# REV1.net
KiCad netlist of a schematic drawn in EAGLE
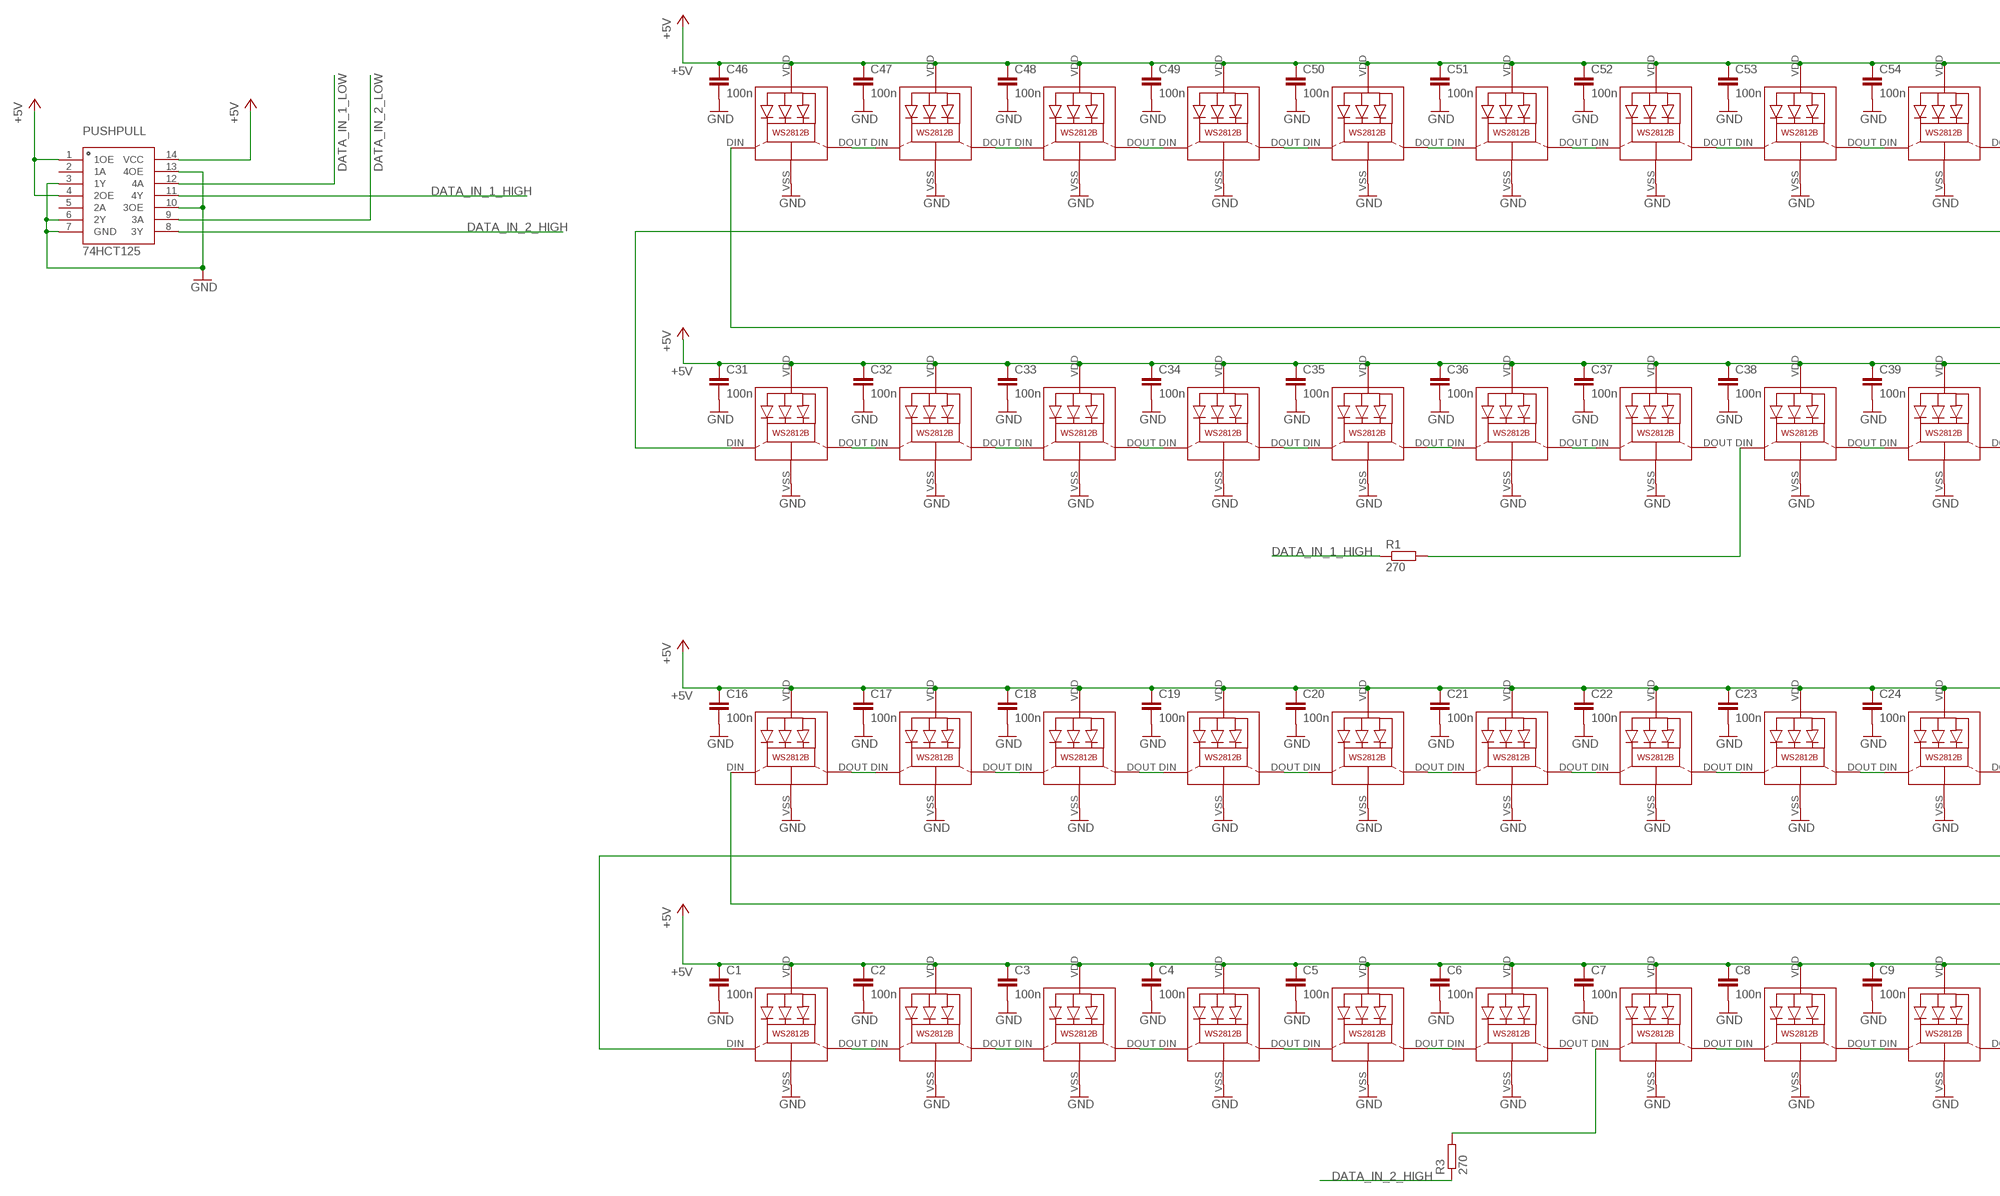
[diagram p0: schematic, sheet 1, part 1 of 2]
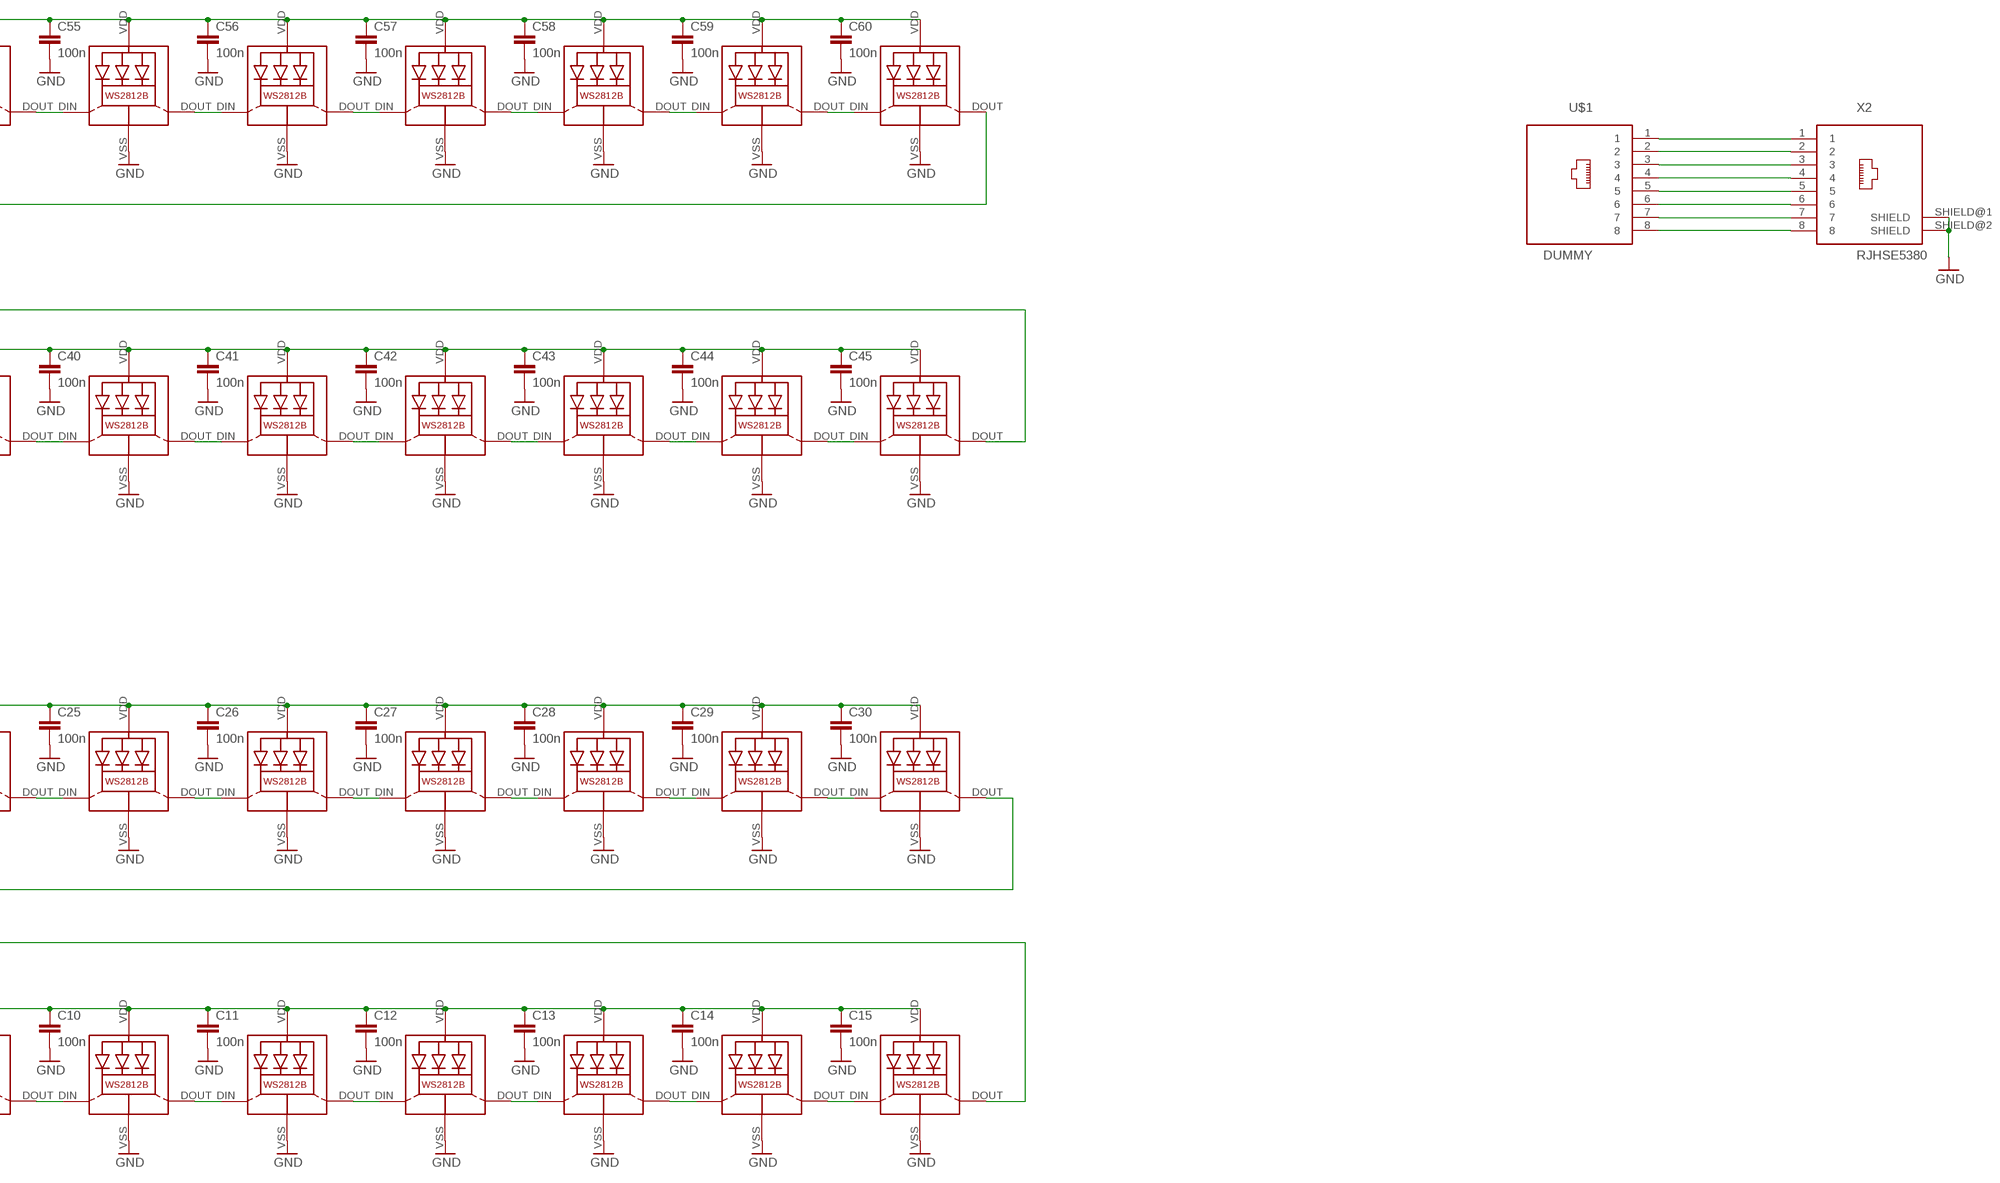
[diagram p1: schematic, sheet 1, part 2 of 2]
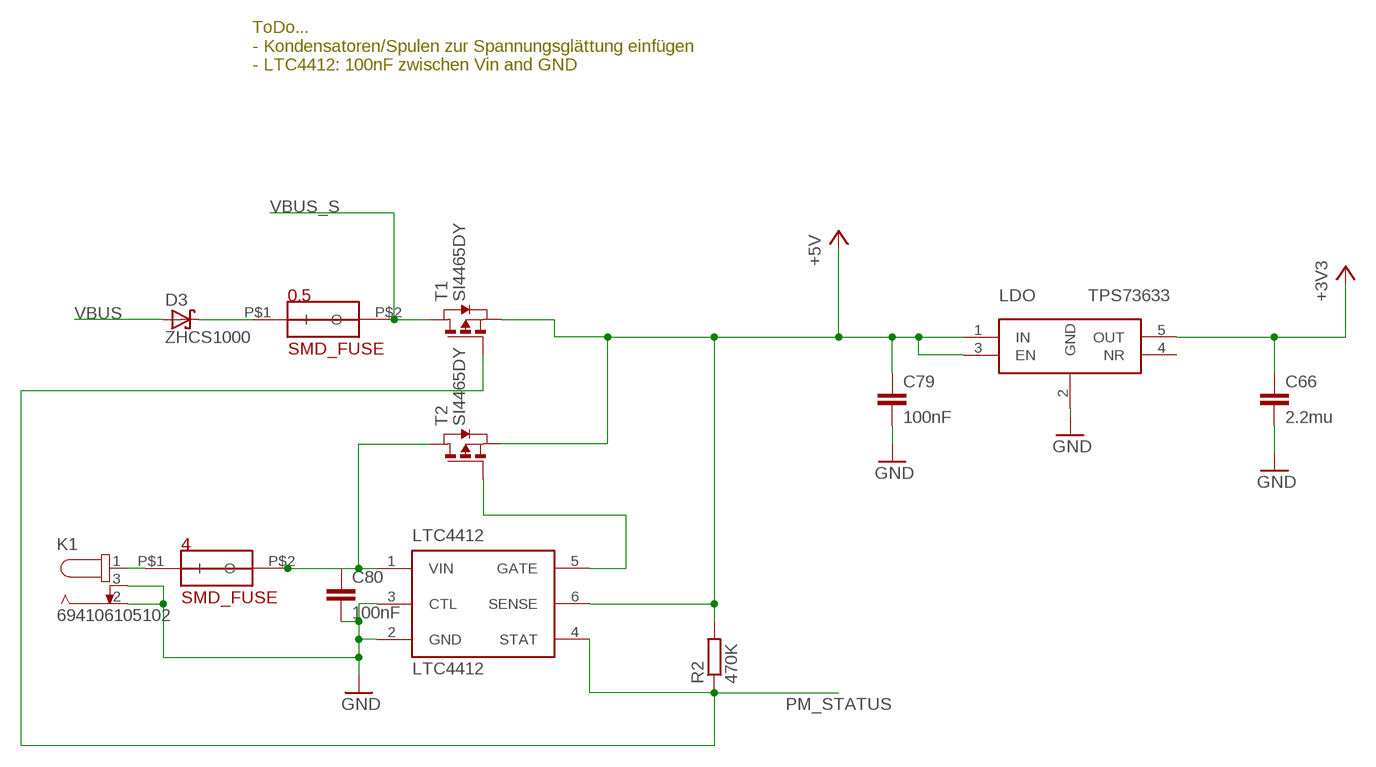
[diagram p2: schematic, sheet 2]
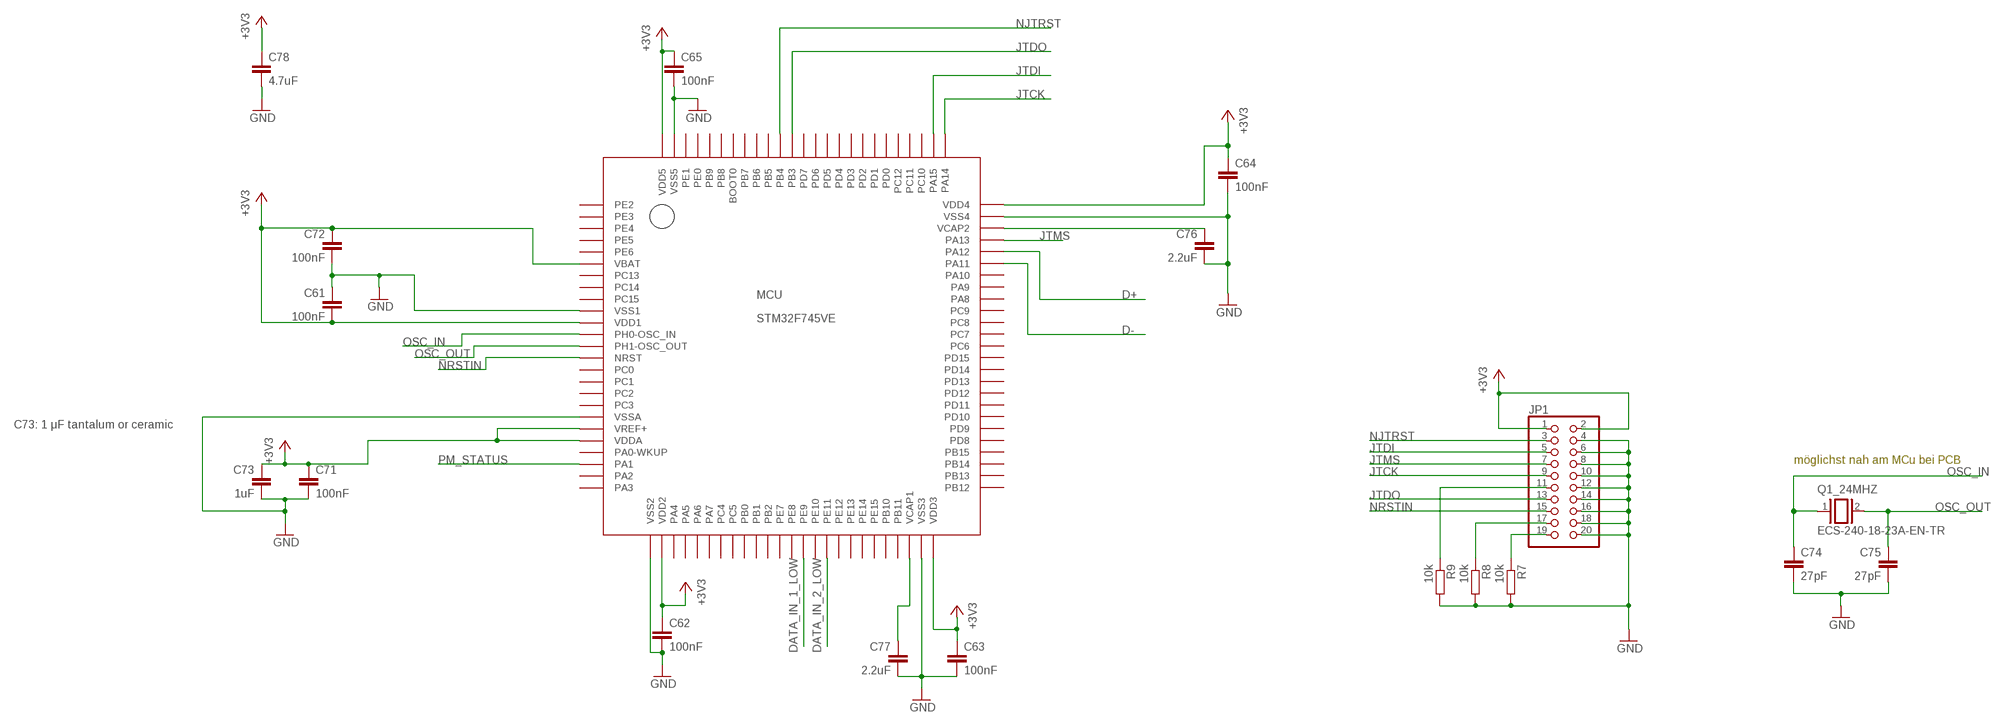
[diagram p3: schematic, sheet 3]
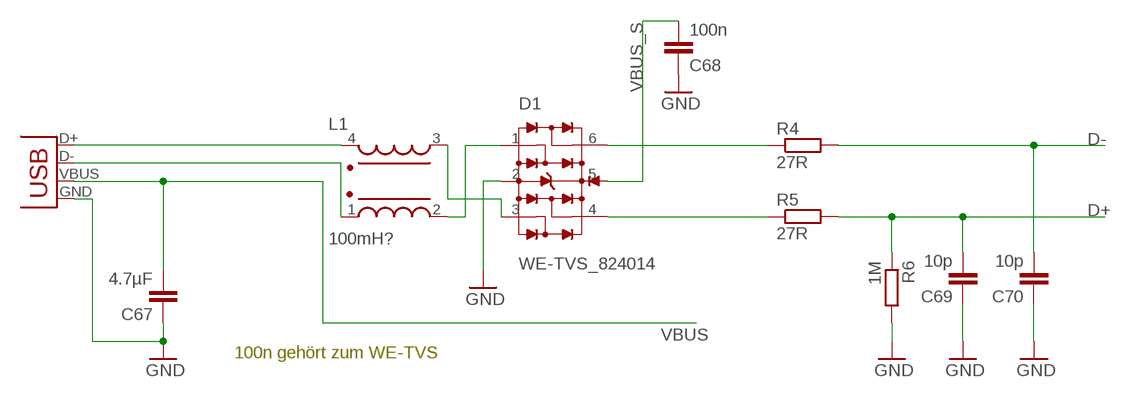
[diagram p4: schematic, sheet 4]

(export (version "E")
  (design (tool "Eeschema 10.0.6"))
  (components
    (comp (ref "C61")
      (value "100nF")
      (footprint "eagle-import:C0603")
      (libsource (lib "eagle-import") (part "C-EUC0603"))
    )
    (comp (ref "C62")
      (value "100nF")
      (footprint "eagle-import:C0603")
      (libsource (lib "eagle-import") (part "C-EUC0603"))
    )
    (comp (ref "C63")
      (value "100nF")
      (footprint "eagle-import:C0603")
      (libsource (lib "eagle-import") (part "C-EUC0603"))
    )
    (comp (ref "C64")
      (value "100nF")
      (footprint "eagle-import:C0603")
      (libsource (lib "eagle-import") (part "C-EUC0603"))
    )
    (comp (ref "C65")
      (value "100nF")
      (footprint "eagle-import:C0603")
      (libsource (lib "eagle-import") (part "C-EUC0603"))
    )
    (comp (ref "C71")
      (value "100nF")
      (footprint "eagle-import:C0603")
      (libsource (lib "eagle-import") (part "C-EUC0603"))
    )
    (comp (ref "C72")
      (value "100nF")
      (footprint "eagle-import:C0603")
      (libsource (lib "eagle-import") (part "C-EUC0603"))
    )
    (comp (ref "C73")
      (value "1uF")
      (footprint "eagle-import:C0603")
      (libsource (lib "eagle-import") (part "C-EUC0603"))
    )
    (comp (ref "C74")
      (value "27pF")
      (footprint "eagle-import:C0603")
      (libsource (lib "eagle-import") (part "C-EUC0603"))
    )
    (comp (ref "C75")
      (value "27pF")
      (footprint "eagle-import:C0603")
      (libsource (lib "eagle-import") (part "C-EUC0603"))
    )
    (comp (ref "C76")
      (value "2.2uF")
      (footprint "eagle-import:C0603")
      (libsource (lib "eagle-import") (part "C-EUC0603"))
    )
    (comp (ref "C77")
      (value "2.2uF")
      (footprint "eagle-import:C0603")
      (libsource (lib "eagle-import") (part "C-EUC0603"))
    )
    (comp (ref "C78")
      (value "4.7uF")
      (footprint "eagle-import:C0603")
      (libsource (lib "eagle-import") (part "C-EUC0603"))
    )
    (comp (ref "JP1")
      (value "PINHD-2X10_2.54-SMD")
      (footprint "eagle-import:2X10SMD")
      (libsource (lib "eagle-import") (part "PINHD-2X10_2.54-SMD"))
    )
    (comp (ref "MCU")
      (value "STM32F745VE")
      (footprint "eagle-import:LQFP100")
      (libsource (lib "eagle-import") (part "STM32F745VE"))
    )
    (comp (ref "Q1_24MHZ")
      (value "ECS-240-18-23A-EN-TR")
      (footprint "eagle-import:ESC64A")
      (libsource (lib "eagle-import") (part "ECX64A"))
    )
    (comp (ref "R7")
      (value "10k")
      (footprint "eagle-import:R0603")
      (libsource (lib "eagle-import") (part "R-EU_R0603"))
    )
    (comp (ref "R8")
      (value "10k")
      (footprint "eagle-import:R0603")
      (libsource (lib "eagle-import") (part "R-EU_R0603"))
    )
    (comp (ref "R9")
      (value "10k")
      (footprint "eagle-import:R0603")
      (libsource (lib "eagle-import") (part "R-EU_R0603"))
    )
    (comp (ref "C1")
      (value "100n")
      (footprint "eagle-import:C0603")
      (libsource (lib "eagle-import") (part "C-EUC0603"))
    )
    (comp (ref "C2")
      (value "100n")
      (footprint "eagle-import:C0603")
      (libsource (lib "eagle-import") (part "C-EUC0603"))
    )
    (comp (ref "C3")
      (value "100n")
      (footprint "eagle-import:C0603")
      (libsource (lib "eagle-import") (part "C-EUC0603"))
    )
    (comp (ref "C4")
      (value "100n")
      (footprint "eagle-import:C0603")
      (libsource (lib "eagle-import") (part "C-EUC0603"))
    )
    (comp (ref "C5")
      (value "100n")
      (footprint "eagle-import:C0603")
      (libsource (lib "eagle-import") (part "C-EUC0603"))
    )
    (comp (ref "C6")
      (value "100n")
      (footprint "eagle-import:C0603")
      (libsource (lib "eagle-import") (part "C-EUC0603"))
    )
    (comp (ref "C7")
      (value "100n")
      (footprint "eagle-import:C0603")
      (libsource (lib "eagle-import") (part "C-EUC0603"))
    )
    (comp (ref "C8")
      (value "100n")
      (footprint "eagle-import:C0603")
      (libsource (lib "eagle-import") (part "C-EUC0603"))
    )
    (comp (ref "C9")
      (value "100n")
      (footprint "eagle-import:C0603")
      (libsource (lib "eagle-import") (part "C-EUC0603"))
    )
    (comp (ref "C10")
      (value "100n")
      (footprint "eagle-import:C0603")
      (libsource (lib "eagle-import") (part "C-EUC0603"))
    )
    (comp (ref "C11")
      (value "100n")
      (footprint "eagle-import:C0603")
      (libsource (lib "eagle-import") (part "C-EUC0603"))
    )
    (comp (ref "C12")
      (value "100n")
      (footprint "eagle-import:C0603")
      (libsource (lib "eagle-import") (part "C-EUC0603"))
    )
    (comp (ref "C13")
      (value "100n")
      (footprint "eagle-import:C0603")
      (libsource (lib "eagle-import") (part "C-EUC0603"))
    )
    (comp (ref "C14")
      (value "100n")
      (footprint "eagle-import:C0603")
      (libsource (lib "eagle-import") (part "C-EUC0603"))
    )
    (comp (ref "C15")
      (value "100n")
      (footprint "eagle-import:C0603")
      (libsource (lib "eagle-import") (part "C-EUC0603"))
    )
    (comp (ref "C16")
      (value "100n")
      (footprint "eagle-import:C0603")
      (libsource (lib "eagle-import") (part "C-EUC0603"))
    )
    (comp (ref "C17")
      (value "100n")
      (footprint "eagle-import:C0603")
      (libsource (lib "eagle-import") (part "C-EUC0603"))
    )
    (comp (ref "C18")
      (value "100n")
      (footprint "eagle-import:C0603")
      (libsource (lib "eagle-import") (part "C-EUC0603"))
    )
    (comp (ref "C19")
      (value "100n")
      (footprint "eagle-import:C0603")
      (libsource (lib "eagle-import") (part "C-EUC0603"))
    )
    (comp (ref "C20")
      (value "100n")
      (footprint "eagle-import:C0603")
      (libsource (lib "eagle-import") (part "C-EUC0603"))
    )
    (comp (ref "C21")
      (value "100n")
      (footprint "eagle-import:C0603")
      (libsource (lib "eagle-import") (part "C-EUC0603"))
    )
    (comp (ref "C22")
      (value "100n")
      (footprint "eagle-import:C0603")
      (libsource (lib "eagle-import") (part "C-EUC0603"))
    )
    (comp (ref "C23")
      (value "100n")
      (footprint "eagle-import:C0603")
      (libsource (lib "eagle-import") (part "C-EUC0603"))
    )
    (comp (ref "C24")
      (value "100n")
      (footprint "eagle-import:C0603")
      (libsource (lib "eagle-import") (part "C-EUC0603"))
    )
    (comp (ref "C25")
      (value "100n")
      (footprint "eagle-import:C0603")
      (libsource (lib "eagle-import") (part "C-EUC0603"))
    )
    (comp (ref "C26")
      (value "100n")
      (footprint "eagle-import:C0603")
      (libsource (lib "eagle-import") (part "C-EUC0603"))
    )
    (comp (ref "C27")
      (value "100n")
      (footprint "eagle-import:C0603")
      (libsource (lib "eagle-import") (part "C-EUC0603"))
    )
    (comp (ref "C28")
      (value "100n")
      (footprint "eagle-import:C0603")
      (libsource (lib "eagle-import") (part "C-EUC0603"))
    )
    (comp (ref "C29")
      (value "100n")
      (footprint "eagle-import:C0603")
      (libsource (lib "eagle-import") (part "C-EUC0603"))
    )
    (comp (ref "C30")
      (value "100n")
      (footprint "eagle-import:C0603")
      (libsource (lib "eagle-import") (part "C-EUC0603"))
    )
    (comp (ref "C31")
      (value "100n")
      (footprint "eagle-import:C0603")
      (libsource (lib "eagle-import") (part "C-EUC0603"))
    )
    (comp (ref "C32")
      (value "100n")
      (footprint "eagle-import:C0603")
      (libsource (lib "eagle-import") (part "C-EUC0603"))
    )
    (comp (ref "C33")
      (value "100n")
      (footprint "eagle-import:C0603")
      (libsource (lib "eagle-import") (part "C-EUC0603"))
    )
    (comp (ref "C34")
      (value "100n")
      (footprint "eagle-import:C0603")
      (libsource (lib "eagle-import") (part "C-EUC0603"))
    )
    (comp (ref "C35")
      (value "100n")
      (footprint "eagle-import:C0603")
      (libsource (lib "eagle-import") (part "C-EUC0603"))
    )
    (comp (ref "C36")
      (value "100n")
      (footprint "eagle-import:C0603")
      (libsource (lib "eagle-import") (part "C-EUC0603"))
    )
    (comp (ref "C37")
      (value "100n")
      (footprint "eagle-import:C0603")
      (libsource (lib "eagle-import") (part "C-EUC0603"))
    )
    (comp (ref "C38")
      (value "100n")
      (footprint "eagle-import:C0603")
      (libsource (lib "eagle-import") (part "C-EUC0603"))
    )
    (comp (ref "C39")
      (value "100n")
      (footprint "eagle-import:C0603")
      (libsource (lib "eagle-import") (part "C-EUC0603"))
    )
    (comp (ref "C40")
      (value "100n")
      (footprint "eagle-import:C0603")
      (libsource (lib "eagle-import") (part "C-EUC0603"))
    )
    (comp (ref "C41")
      (value "100n")
      (footprint "eagle-import:C0603")
      (libsource (lib "eagle-import") (part "C-EUC0603"))
    )
    (comp (ref "C42")
      (value "100n")
      (footprint "eagle-import:C0603")
      (libsource (lib "eagle-import") (part "C-EUC0603"))
    )
    (comp (ref "C43")
      (value "100n")
      (footprint "eagle-import:C0603")
      (libsource (lib "eagle-import") (part "C-EUC0603"))
    )
    (comp (ref "C44")
      (value "100n")
      (footprint "eagle-import:C0603")
      (libsource (lib "eagle-import") (part "C-EUC0603"))
    )
    (comp (ref "C45")
      (value "100n")
      (footprint "eagle-import:C0603")
      (libsource (lib "eagle-import") (part "C-EUC0603"))
    )
    (comp (ref "C46")
      (value "100n")
      (footprint "eagle-import:C0603")
      (libsource (lib "eagle-import") (part "C-EUC0603"))
    )
    (comp (ref "C47")
      (value "100n")
      (footprint "eagle-import:C0603")
      (libsource (lib "eagle-import") (part "C-EUC0603"))
    )
    (comp (ref "C48")
      (value "100n")
      (footprint "eagle-import:C0603")
      (libsource (lib "eagle-import") (part "C-EUC0603"))
    )
    (comp (ref "C49")
      (value "100n")
      (footprint "eagle-import:C0603")
      (libsource (lib "eagle-import") (part "C-EUC0603"))
    )
    (comp (ref "C50")
      (value "100n")
      (footprint "eagle-import:C0603")
      (libsource (lib "eagle-import") (part "C-EUC0603"))
    )
    (comp (ref "C51")
      (value "100n")
      (footprint "eagle-import:C0603")
      (libsource (lib "eagle-import") (part "C-EUC0603"))
    )
    (comp (ref "C52")
      (value "100n")
      (footprint "eagle-import:C0603")
      (libsource (lib "eagle-import") (part "C-EUC0603"))
    )
    (comp (ref "C53")
      (value "100n")
      (footprint "eagle-import:C0603")
      (libsource (lib "eagle-import") (part "C-EUC0603"))
    )
    (comp (ref "C54")
      (value "100n")
      (footprint "eagle-import:C0603")
      (libsource (lib "eagle-import") (part "C-EUC0603"))
    )
    (comp (ref "C55")
      (value "100n")
      (footprint "eagle-import:C0603")
      (libsource (lib "eagle-import") (part "C-EUC0603"))
    )
    (comp (ref "C56")
      (value "100n")
      (footprint "eagle-import:C0603")
      (libsource (lib "eagle-import") (part "C-EUC0603"))
    )
    (comp (ref "C57")
      (value "100n")
      (footprint "eagle-import:C0603")
      (libsource (lib "eagle-import") (part "C-EUC0603"))
    )
    (comp (ref "C58")
      (value "100n")
      (footprint "eagle-import:C0603")
      (libsource (lib "eagle-import") (part "C-EUC0603"))
    )
    (comp (ref "C59")
      (value "100n")
      (footprint "eagle-import:C0603")
      (libsource (lib "eagle-import") (part "C-EUC0603"))
    )
    (comp (ref "C60")
      (value "100n")
      (footprint "eagle-import:C0603")
      (libsource (lib "eagle-import") (part "C-EUC0603"))
    )
    (comp (ref "LED1")
      (value "WS2812B")
      (footprint "eagle-import:WS2812B")
      (libsource (lib "eagle-import") (part "WS2812B"))
    )
    (comp (ref "LED2")
      (value "WS2812B")
      (footprint "eagle-import:WS2812B")
      (libsource (lib "eagle-import") (part "WS2812B"))
    )
    (comp (ref "LED3")
      (value "WS2812B")
      (footprint "eagle-import:WS2812B")
      (libsource (lib "eagle-import") (part "WS2812B"))
    )
    (comp (ref "LED4")
      (value "WS2812B")
      (footprint "eagle-import:WS2812B")
      (libsource (lib "eagle-import") (part "WS2812B"))
    )
    (comp (ref "LED5")
      (value "WS2812B")
      (footprint "eagle-import:WS2812B")
      (libsource (lib "eagle-import") (part "WS2812B"))
    )
    (comp (ref "LED6")
      (value "WS2812B")
      (footprint "eagle-import:WS2812B")
      (libsource (lib "eagle-import") (part "WS2812B"))
    )
    (comp (ref "LED7")
      (value "WS2812B")
      (footprint "eagle-import:WS2812B")
      (libsource (lib "eagle-import") (part "WS2812B"))
    )
    (comp (ref "LED8")
      (value "WS2812B")
      (footprint "eagle-import:WS2812B")
      (libsource (lib "eagle-import") (part "WS2812B"))
    )
    (comp (ref "LED9")
      (value "WS2812B")
      (footprint "eagle-import:WS2812B")
      (libsource (lib "eagle-import") (part "WS2812B"))
    )
    (comp (ref "LED10")
      (value "WS2812B")
      (footprint "eagle-import:WS2812B")
      (libsource (lib "eagle-import") (part "WS2812B"))
    )
    (comp (ref "LED11")
      (value "WS2812B")
      (footprint "eagle-import:WS2812B")
      (libsource (lib "eagle-import") (part "WS2812B"))
    )
    (comp (ref "LED12")
      (value "WS2812B")
      (footprint "eagle-import:WS2812B")
      (libsource (lib "eagle-import") (part "WS2812B"))
    )
    (comp (ref "LED13")
      (value "WS2812B")
      (footprint "eagle-import:WS2812B")
      (libsource (lib "eagle-import") (part "WS2812B"))
    )
    (comp (ref "LED14")
      (value "WS2812B")
      (footprint "eagle-import:WS2812B")
      (libsource (lib "eagle-import") (part "WS2812B"))
    )
    (comp (ref "LED15")
      (value "WS2812B")
      (footprint "eagle-import:WS2812B")
      (libsource (lib "eagle-import") (part "WS2812B"))
    )
    (comp (ref "LED16")
      (value "WS2812B")
      (footprint "eagle-import:WS2812B")
      (libsource (lib "eagle-import") (part "WS2812B"))
    )
    (comp (ref "LED17")
      (value "WS2812B")
      (footprint "eagle-import:WS2812B")
      (libsource (lib "eagle-import") (part "WS2812B"))
    )
    (comp (ref "LED18")
      (value "WS2812B")
      (footprint "eagle-import:WS2812B")
      (libsource (lib "eagle-import") (part "WS2812B"))
    )
    (comp (ref "LED19")
      (value "WS2812B")
      (footprint "eagle-import:WS2812B")
      (libsource (lib "eagle-import") (part "WS2812B"))
    )
    (comp (ref "LED20")
      (value "WS2812B")
      (footprint "eagle-import:WS2812B")
      (libsource (lib "eagle-import") (part "WS2812B"))
    )
    (comp (ref "LED21")
      (value "WS2812B")
      (footprint "eagle-import:WS2812B")
      (libsource (lib "eagle-import") (part "WS2812B"))
    )
    (comp (ref "LED22")
      (value "WS2812B")
      (footprint "eagle-import:WS2812B")
      (libsource (lib "eagle-import") (part "WS2812B"))
    )
    (comp (ref "LED23")
      (value "WS2812B")
      (footprint "eagle-import:WS2812B")
      (libsource (lib "eagle-import") (part "WS2812B"))
    )
    (comp (ref "LED24")
      (value "WS2812B")
      (footprint "eagle-import:WS2812B")
      (libsource (lib "eagle-import") (part "WS2812B"))
    )
    (comp (ref "LED25")
      (value "WS2812B")
      (footprint "eagle-import:WS2812B")
      (libsource (lib "eagle-import") (part "WS2812B"))
    )
    (comp (ref "LED26")
      (value "WS2812B")
      (footprint "eagle-import:WS2812B")
      (libsource (lib "eagle-import") (part "WS2812B"))
    )
    (comp (ref "LED27")
      (value "WS2812B")
      (footprint "eagle-import:WS2812B")
      (libsource (lib "eagle-import") (part "WS2812B"))
    )
    (comp (ref "LED28")
      (value "WS2812B")
      (footprint "eagle-import:WS2812B")
      (libsource (lib "eagle-import") (part "WS2812B"))
    )
    (comp (ref "LED29")
      (value "WS2812B")
      (footprint "eagle-import:WS2812B")
      (libsource (lib "eagle-import") (part "WS2812B"))
    )
    (comp (ref "LED30")
      (value "WS2812B")
      (footprint "eagle-import:WS2812B")
      (libsource (lib "eagle-import") (part "WS2812B"))
    )
    (comp (ref "LED31")
      (value "WS2812B")
      (footprint "eagle-import:WS2812B")
      (libsource (lib "eagle-import") (part "WS2812B"))
    )
    (comp (ref "LED32")
      (value "WS2812B")
      (footprint "eagle-import:WS2812B")
      (libsource (lib "eagle-import") (part "WS2812B"))
    )
    (comp (ref "LED33")
      (value "WS2812B")
      (footprint "eagle-import:WS2812B")
      (libsource (lib "eagle-import") (part "WS2812B"))
    )
    (comp (ref "LED34")
      (value "WS2812B")
      (footprint "eagle-import:WS2812B")
      (libsource (lib "eagle-import") (part "WS2812B"))
    )
    (comp (ref "LED35")
      (value "WS2812B")
      (footprint "eagle-import:WS2812B")
      (libsource (lib "eagle-import") (part "WS2812B"))
    )
    (comp (ref "LED36")
      (value "WS2812B")
      (footprint "eagle-import:WS2812B")
      (libsource (lib "eagle-import") (part "WS2812B"))
    )
    (comp (ref "LED37")
      (value "WS2812B")
      (footprint "eagle-import:WS2812B")
      (libsource (lib "eagle-import") (part "WS2812B"))
    )
    (comp (ref "LED38")
      (value "WS2812B")
      (footprint "eagle-import:WS2812B")
      (libsource (lib "eagle-import") (part "WS2812B"))
    )
    (comp (ref "LED39")
      (value "WS2812B")
      (footprint "eagle-import:WS2812B")
      (libsource (lib "eagle-import") (part "WS2812B"))
    )
    (comp (ref "LED40")
      (value "WS2812B")
      (footprint "eagle-import:WS2812B")
      (libsource (lib "eagle-import") (part "WS2812B"))
    )
    (comp (ref "LED41")
      (value "WS2812B")
      (footprint "eagle-import:WS2812B")
      (libsource (lib "eagle-import") (part "WS2812B"))
    )
    (comp (ref "LED42")
      (value "WS2812B")
      (footprint "eagle-import:WS2812B")
      (libsource (lib "eagle-import") (part "WS2812B"))
    )
    (comp (ref "LED43")
      (value "WS2812B")
      (footprint "eagle-import:WS2812B")
      (libsource (lib "eagle-import") (part "WS2812B"))
    )
    (comp (ref "LED44")
      (value "WS2812B")
      (footprint "eagle-import:WS2812B")
      (libsource (lib "eagle-import") (part "WS2812B"))
    )
    (comp (ref "LED45")
      (value "WS2812B")
      (footprint "eagle-import:WS2812B")
      (libsource (lib "eagle-import") (part "WS2812B"))
    )
    (comp (ref "LED46")
      (value "WS2812B")
      (footprint "eagle-import:WS2812B")
      (libsource (lib "eagle-import") (part "WS2812B"))
    )
    (comp (ref "LED47")
      (value "WS2812B")
      (footprint "eagle-import:WS2812B")
      (libsource (lib "eagle-import") (part "WS2812B"))
    )
    (comp (ref "LED48")
      (value "WS2812B")
      (footprint "eagle-import:WS2812B")
      (libsource (lib "eagle-import") (part "WS2812B"))
    )
    (comp (ref "LED49")
      (value "WS2812B")
      (footprint "eagle-import:WS2812B")
      (libsource (lib "eagle-import") (part "WS2812B"))
    )
    (comp (ref "LED50")
      (value "WS2812B")
      (footprint "eagle-import:WS2812B")
      (libsource (lib "eagle-import") (part "WS2812B"))
    )
    (comp (ref "LED51")
      (value "WS2812B")
      (footprint "eagle-import:WS2812B")
      (libsource (lib "eagle-import") (part "WS2812B"))
    )
    (comp (ref "LED52")
      (value "WS2812B")
      (footprint "eagle-import:WS2812B")
      (libsource (lib "eagle-import") (part "WS2812B"))
    )
    (comp (ref "LED53")
      (value "WS2812B")
      (footprint "eagle-import:WS2812B")
      (libsource (lib "eagle-import") (part "WS2812B"))
    )
    (comp (ref "LED54")
      (value "WS2812B")
      (footprint "eagle-import:WS2812B")
      (libsource (lib "eagle-import") (part "WS2812B"))
    )
    (comp (ref "LED55")
      (value "WS2812B")
      (footprint "eagle-import:WS2812B")
      (libsource (lib "eagle-import") (part "WS2812B"))
    )
    (comp (ref "LED56")
      (value "WS2812B")
      (footprint "eagle-import:WS2812B")
      (libsource (lib "eagle-import") (part "WS2812B"))
    )
    (comp (ref "LED57")
      (value "WS2812B")
      (footprint "eagle-import:WS2812B")
      (libsource (lib "eagle-import") (part "WS2812B"))
    )
    (comp (ref "LED58")
      (value "WS2812B")
      (footprint "eagle-import:WS2812B")
      (libsource (lib "eagle-import") (part "WS2812B"))
    )
    (comp (ref "LED59")
      (value "WS2812B")
      (footprint "eagle-import:WS2812B")
      (libsource (lib "eagle-import") (part "WS2812B"))
    )
    (comp (ref "LED60")
      (value "WS2812B")
      (footprint "eagle-import:WS2812B")
      (libsource (lib "eagle-import") (part "WS2812B"))
    )
    (comp (ref "PUSHPULL")
      (value "74HCT125")
      (footprint "eagle-import:SO-14DW")
      (libsource (lib "eagle-import") (part "74HCT125"))
    )
    (comp (ref "R1")
      (value "270")
      (footprint "eagle-import:R0603")
      (libsource (lib "eagle-import") (part "R-EU_R0603"))
    )
    (comp (ref "R3")
      (value "270")
      (footprint "eagle-import:R0603")
      (libsource (lib "eagle-import") (part "R-EU_R0603"))
    )
    (comp (ref "U$1")
      (value "DUMMY")
      (footprint "eagle-import:DUMMY")
      (libsource (lib "eagle-import") (part "DUMMY"))
    )
    (comp (ref "X2")
      (value "RJHSE5380")
      (footprint "eagle-import:RJHSE5380")
      (libsource (lib "eagle-import") (part "RJHSE5380"))
    )
    (comp (ref "C67")
      (value "4.7µF")
      (footprint "eagle-import:C0603")
      (libsource (lib "eagle-import") (part "C-EUC0603"))
    )
    (comp (ref "C68")
      (value "100n")
      (footprint "eagle-import:C0603")
      (libsource (lib "eagle-import") (part "C-EUC0603"))
    )
    (comp (ref "C69")
      (value "10p")
      (footprint "eagle-import:C0603")
      (libsource (lib "eagle-import") (part "C-EUC0603"))
    )
    (comp (ref "C70")
      (value "10p")
      (footprint "eagle-import:C0603")
      (libsource (lib "eagle-import") (part "C-EUC0603"))
    )
    (comp (ref "D1")
      (value "WE-TVS_824014")
      (footprint "eagle-import:WE-TVS_SOT23-6L")
      (libsource (lib "eagle-import") (part "WE-TVS_824014"))
    )
    (comp (ref "L1")
      (value "100mH?")
      (footprint "eagle-import:WE-CNSW_0805")
      (libsource (lib "eagle-import") (part "WE-CNSW_0805"))
    )
    (comp (ref "R4")
      (value "27R")
      (footprint "eagle-import:R0603")
      (libsource (lib "eagle-import") (part "R-EU_R0603"))
    )
    (comp (ref "R5")
      (value "27R")
      (footprint "eagle-import:R0603")
      (libsource (lib "eagle-import") (part "R-EU_R0603"))
    )
    (comp (ref "R6")
      (value "1M")
      (footprint "eagle-import:R0603")
      (libsource (lib "eagle-import") (part "R-EU_R0603"))
    )
    (comp (ref "X1")
      (value "USBSMD")
      (footprint "eagle-import:USB-MINIB")
      (libsource (lib "eagle-import") (part "USBSMD"))
    )
    (comp (ref "0.5")
      (value "SMD_FUSE")
      (footprint "eagle-import:FUSE")
      (libsource (lib "eagle-import") (part "SMD_FUSE"))
    )
    (comp (ref "4")
      (value "SMD_FUSE")
      (footprint "eagle-import:FUSE")
      (libsource (lib "eagle-import") (part "SMD_FUSE"))
    )
    (comp (ref "C66")
      (value "2.2mu")
      (footprint "eagle-import:C0603")
      (libsource (lib "eagle-import") (part "C-EUC0603"))
    )
    (comp (ref "C79")
      (value "100nF")
      (footprint "eagle-import:C0603")
      (libsource (lib "eagle-import") (part "C-EUC0603"))
    )
    (comp (ref "C80")
      (value "100nF")
      (footprint "eagle-import:C0603")
      (libsource (lib "eagle-import") (part "C-EUC0603"))
    )
    (comp (ref "D3")
      (value "ZHCS1000")
      (footprint "eagle-import:SOT23")
      (libsource (lib "eagle-import") (part "ZHCS1000"))
    )
    (comp (ref "K1")
      (value "694106105102")
      (footprint "eagle-import:694106105102")
      (libsource (lib "eagle-import") (part "694106105102"))
    )
    (comp (ref "LDO")
      (value "TPS73633")
      (footprint "eagle-import:SOT23-DBV")
      (libsource (lib "eagle-import") (part "TPS73633"))
    )
    (comp (ref "LTC4412")
      (value "LTC4412")
      (footprint "eagle-import:SOT23-6L")
      (libsource (lib "eagle-import") (part "LTC4412"))
    )
    (comp (ref "R2")
      (value "470K")
      (footprint "eagle-import:R0603")
      (libsource (lib "eagle-import") (part "R-EU_R0603"))
    )
    (comp (ref "T1")
      (value "SI4465DY")
      (footprint "eagle-import:SO08")
      (libsource (lib "eagle-import") (part "PMOSSOT223SO8"))
    )
    (comp (ref "T2")
      (value "SI4465DY")
      (footprint "eagle-import:SO08")
      (libsource (lib "eagle-import") (part "PMOSSOT223SO8"))
    )
  )
  (nets
    (net (code "1") (name "+3V3") (class "Default")
      (node (ref "C61") (pin "2") (pinfunction "2_2") (pintype "passive"))
      (node (ref "C62") (pin "1") (pinfunction "1_1") (pintype "passive"))
      (node (ref "C63") (pin "1") (pinfunction "1_1") (pintype "passive"))
      (node (ref "C64") (pin "1") (pinfunction "1_1") (pintype "passive"))
      (node (ref "C65") (pin "1") (pinfunction "1_1") (pintype "passive"))
      (node (ref "C66") (pin "1") (pinfunction "1_1") (pintype "passive"))
      (node (ref "C71") (pin "1") (pinfunction "1_1") (pintype "passive"))
      (node (ref "C72") (pin "1") (pinfunction "1_1") (pintype "passive"))
      (node (ref "C73") (pin "1") (pinfunction "1_1") (pintype "passive"))
      (node (ref "C78") (pin "1") (pinfunction "1_1") (pintype "passive"))
      (node (ref "JP1") (pin "1") (pinfunction "1_1") (pintype "passive"))
      (node (ref "JP1") (pin "2") (pinfunction "2_2") (pintype "passive"))
      (node (ref "LDO") (pin "5") (pinfunction "OUT_5") (pintype "bidirectional"))
      (node (ref "MCU") (pin "100") (pinfunction "VDD5_100") (pintype "power_in"))
      (node (ref "MCU") (pin "11") (pinfunction "VDD1_11") (pintype "power_in"))
      (node (ref "MCU") (pin "20") (pinfunction "VREF+_20") (pintype "power_in"))
      (node (ref "MCU") (pin "21") (pinfunction "VDDA_21") (pintype "power_in"))
      (node (ref "MCU") (pin "27") (pinfunction "VDD2_27") (pintype "power_in"))
      (node (ref "MCU") (pin "50") (pinfunction "VDD3_50") (pintype "power_in"))
      (node (ref "MCU") (pin "6") (pinfunction "VBAT_6") (pintype "power_in"))
      (node (ref "MCU") (pin "75") (pinfunction "VDD4_75") (pintype "power_in"))
    )
    (net (code "2") (name "+5V") (class "Default")
      (node (ref "C1") (pin "1") (pinfunction "1_1") (pintype "passive"))
      (node (ref "C10") (pin "1") (pinfunction "1_1") (pintype "passive"))
      (node (ref "C11") (pin "1") (pinfunction "1_1") (pintype "passive"))
      (node (ref "C12") (pin "1") (pinfunction "1_1") (pintype "passive"))
      (node (ref "C13") (pin "1") (pinfunction "1_1") (pintype "passive"))
      (node (ref "C14") (pin "1") (pinfunction "1_1") (pintype "passive"))
      (node (ref "C15") (pin "1") (pinfunction "1_1") (pintype "passive"))
      (node (ref "C16") (pin "1") (pinfunction "1_1") (pintype "passive"))
      (node (ref "C17") (pin "1") (pinfunction "1_1") (pintype "passive"))
      (node (ref "C18") (pin "1") (pinfunction "1_1") (pintype "passive"))
      (node (ref "C19") (pin "1") (pinfunction "1_1") (pintype "passive"))
      (node (ref "C2") (pin "1") (pinfunction "1_1") (pintype "passive"))
      (node (ref "C20") (pin "1") (pinfunction "1_1") (pintype "passive"))
      (node (ref "C21") (pin "1") (pinfunction "1_1") (pintype "passive"))
      (node (ref "C22") (pin "1") (pinfunction "1_1") (pintype "passive"))
      (node (ref "C23") (pin "1") (pinfunction "1_1") (pintype "passive"))
      (node (ref "C24") (pin "1") (pinfunction "1_1") (pintype "passive"))
      (node (ref "C25") (pin "1") (pinfunction "1_1") (pintype "passive"))
      (node (ref "C26") (pin "1") (pinfunction "1_1") (pintype "passive"))
      (node (ref "C27") (pin "1") (pinfunction "1_1") (pintype "passive"))
      (node (ref "C28") (pin "1") (pinfunction "1_1") (pintype "passive"))
      (node (ref "C29") (pin "1") (pinfunction "1_1") (pintype "passive"))
      (node (ref "C3") (pin "1") (pinfunction "1_1") (pintype "passive"))
      (node (ref "C30") (pin "1") (pinfunction "1_1") (pintype "passive"))
      (node (ref "C31") (pin "1") (pinfunction "1_1") (pintype "passive"))
      (node (ref "C32") (pin "1") (pinfunction "1_1") (pintype "passive"))
      (node (ref "C33") (pin "1") (pinfunction "1_1") (pintype "passive"))
      (node (ref "C34") (pin "1") (pinfunction "1_1") (pintype "passive"))
      (node (ref "C35") (pin "1") (pinfunction "1_1") (pintype "passive"))
      (node (ref "C36") (pin "1") (pinfunction "1_1") (pintype "passive"))
      (node (ref "C37") (pin "1") (pinfunction "1_1") (pintype "passive"))
      (node (ref "C38") (pin "1") (pinfunction "1_1") (pintype "passive"))
      (node (ref "C39") (pin "1") (pinfunction "1_1") (pintype "passive"))
      (node (ref "C4") (pin "1") (pinfunction "1_1") (pintype "passive"))
      (node (ref "C40") (pin "1") (pinfunction "1_1") (pintype "passive"))
      (node (ref "C41") (pin "1") (pinfunction "1_1") (pintype "passive"))
      (node (ref "C42") (pin "1") (pinfunction "1_1") (pintype "passive"))
      (node (ref "C43") (pin "1") (pinfunction "1_1") (pintype "passive"))
      (node (ref "C44") (pin "1") (pinfunction "1_1") (pintype "passive"))
      (node (ref "C45") (pin "1") (pinfunction "1_1") (pintype "passive"))
      (node (ref "C46") (pin "1") (pinfunction "1_1") (pintype "passive"))
      (node (ref "C47") (pin "1") (pinfunction "1_1") (pintype "passive"))
      (node (ref "C48") (pin "1") (pinfunction "1_1") (pintype "passive"))
      (node (ref "C49") (pin "1") (pinfunction "1_1") (pintype "passive"))
      (node (ref "C5") (pin "1") (pinfunction "1_1") (pintype "passive"))
      (node (ref "C50") (pin "1") (pinfunction "1_1") (pintype "passive"))
      (node (ref "C51") (pin "1") (pinfunction "1_1") (pintype "passive"))
      (node (ref "C52") (pin "1") (pinfunction "1_1") (pintype "passive"))
      (node (ref "C53") (pin "1") (pinfunction "1_1") (pintype "passive"))
      (node (ref "C54") (pin "1") (pinfunction "1_1") (pintype "passive"))
      (node (ref "C55") (pin "1") (pinfunction "1_1") (pintype "passive"))
      (node (ref "C56") (pin "1") (pinfunction "1_1") (pintype "passive"))
      (node (ref "C57") (pin "1") (pinfunction "1_1") (pintype "passive"))
      (node (ref "C58") (pin "1") (pinfunction "1_1") (pintype "passive"))
      (node (ref "C59") (pin "1") (pinfunction "1_1") (pintype "passive"))
      (node (ref "C6") (pin "1") (pinfunction "1_1") (pintype "passive"))
      (node (ref "C60") (pin "1") (pinfunction "1_1") (pintype "passive"))
      (node (ref "C7") (pin "1") (pinfunction "1_1") (pintype "passive"))
      (node (ref "C79") (pin "1") (pinfunction "1_1") (pintype "passive"))
      (node (ref "C8") (pin "1") (pinfunction "1_1") (pintype "passive"))
      (node (ref "C9") (pin "1") (pinfunction "1_1") (pintype "passive"))
      (node (ref "LDO") (pin "1") (pinfunction "IN_1") (pintype "bidirectional"))
      (node (ref "LDO") (pin "3") (pinfunction "EN_3") (pintype "bidirectional"))
      (node (ref "LED1") (pin "VDD") (pinfunction "VDD_VDD") (pintype "power_in"))
      (node (ref "LED10") (pin "VDD") (pinfunction "VDD_VDD") (pintype "power_in"))
      (node (ref "LED11") (pin "VDD") (pinfunction "VDD_VDD") (pintype "power_in"))
      (node (ref "LED12") (pin "VDD") (pinfunction "VDD_VDD") (pintype "power_in"))
      (node (ref "LED13") (pin "VDD") (pinfunction "VDD_VDD") (pintype "power_in"))
      (node (ref "LED14") (pin "VDD") (pinfunction "VDD_VDD") (pintype "power_in"))
      (node (ref "LED15") (pin "VDD") (pinfunction "VDD_VDD") (pintype "power_in"))
      (node (ref "LED16") (pin "VDD") (pinfunction "VDD_VDD") (pintype "power_in"))
      (node (ref "LED17") (pin "VDD") (pinfunction "VDD_VDD") (pintype "power_in"))
      (node (ref "LED18") (pin "VDD") (pinfunction "VDD_VDD") (pintype "power_in"))
      (node (ref "LED19") (pin "VDD") (pinfunction "VDD_VDD") (pintype "power_in"))
      (node (ref "LED2") (pin "VDD") (pinfunction "VDD_VDD") (pintype "power_in"))
      (node (ref "LED20") (pin "VDD") (pinfunction "VDD_VDD") (pintype "power_in"))
      (node (ref "LED21") (pin "VDD") (pinfunction "VDD_VDD") (pintype "power_in"))
      (node (ref "LED22") (pin "VDD") (pinfunction "VDD_VDD") (pintype "power_in"))
      (node (ref "LED23") (pin "VDD") (pinfunction "VDD_VDD") (pintype "power_in"))
      (node (ref "LED24") (pin "VDD") (pinfunction "VDD_VDD") (pintype "power_in"))
      (node (ref "LED25") (pin "VDD") (pinfunction "VDD_VDD") (pintype "power_in"))
      (node (ref "LED26") (pin "VDD") (pinfunction "VDD_VDD") (pintype "power_in"))
      (node (ref "LED27") (pin "VDD") (pinfunction "VDD_VDD") (pintype "power_in"))
      (node (ref "LED28") (pin "VDD") (pinfunction "VDD_VDD") (pintype "power_in"))
      (node (ref "LED29") (pin "VDD") (pinfunction "VDD_VDD") (pintype "power_in"))
      (node (ref "LED3") (pin "VDD") (pinfunction "VDD_VDD") (pintype "power_in"))
      (node (ref "LED30") (pin "VDD") (pinfunction "VDD_VDD") (pintype "power_in"))
      (node (ref "LED31") (pin "VDD") (pinfunction "VDD_VDD") (pintype "power_in"))
      (node (ref "LED32") (pin "VDD") (pinfunction "VDD_VDD") (pintype "power_in"))
      (node (ref "LED33") (pin "VDD") (pinfunction "VDD_VDD") (pintype "power_in"))
      (node (ref "LED34") (pin "VDD") (pinfunction "VDD_VDD") (pintype "power_in"))
      (node (ref "LED35") (pin "VDD") (pinfunction "VDD_VDD") (pintype "power_in"))
      (node (ref "LED36") (pin "VDD") (pinfunction "VDD_VDD") (pintype "power_in"))
      (node (ref "LED37") (pin "VDD") (pinfunction "VDD_VDD") (pintype "power_in"))
      (node (ref "LED38") (pin "VDD") (pinfunction "VDD_VDD") (pintype "power_in"))
      (node (ref "LED39") (pin "VDD") (pinfunction "VDD_VDD") (pintype "power_in"))
      (node (ref "LED4") (pin "VDD") (pinfunction "VDD_VDD") (pintype "power_in"))
      (node (ref "LED40") (pin "VDD") (pinfunction "VDD_VDD") (pintype "power_in"))
      (node (ref "LED41") (pin "VDD") (pinfunction "VDD_VDD") (pintype "power_in"))
      (node (ref "LED42") (pin "VDD") (pinfunction "VDD_VDD") (pintype "power_in"))
      (node (ref "LED43") (pin "VDD") (pinfunction "VDD_VDD") (pintype "power_in"))
      (node (ref "LED44") (pin "VDD") (pinfunction "VDD_VDD") (pintype "power_in"))
      (node (ref "LED45") (pin "VDD") (pinfunction "VDD_VDD") (pintype "power_in"))
      (node (ref "LED46") (pin "VDD") (pinfunction "VDD_VDD") (pintype "power_in"))
      (node (ref "LED47") (pin "VDD") (pinfunction "VDD_VDD") (pintype "power_in"))
      (node (ref "LED48") (pin "VDD") (pinfunction "VDD_VDD") (pintype "power_in"))
      (node (ref "LED49") (pin "VDD") (pinfunction "VDD_VDD") (pintype "power_in"))
      (node (ref "LED5") (pin "VDD") (pinfunction "VDD_VDD") (pintype "power_in"))
      (node (ref "LED50") (pin "VDD") (pinfunction "VDD_VDD") (pintype "power_in"))
      (node (ref "LED51") (pin "VDD") (pinfunction "VDD_VDD") (pintype "power_in"))
      (node (ref "LED52") (pin "VDD") (pinfunction "VDD_VDD") (pintype "power_in"))
      (node (ref "LED53") (pin "VDD") (pinfunction "VDD_VDD") (pintype "power_in"))
      (node (ref "LED54") (pin "VDD") (pinfunction "VDD_VDD") (pintype "power_in"))
      (node (ref "LED55") (pin "VDD") (pinfunction "VDD_VDD") (pintype "power_in"))
      (node (ref "LED56") (pin "VDD") (pinfunction "VDD_VDD") (pintype "power_in"))
      (node (ref "LED57") (pin "VDD") (pinfunction "VDD_VDD") (pintype "power_in"))
      (node (ref "LED58") (pin "VDD") (pinfunction "VDD_VDD") (pintype "power_in"))
      (node (ref "LED59") (pin "VDD") (pinfunction "VDD_VDD") (pintype "power_in"))
      (node (ref "LED6") (pin "VDD") (pinfunction "VDD_VDD") (pintype "power_in"))
      (node (ref "LED60") (pin "VDD") (pinfunction "VDD_VDD") (pintype "power_in"))
      (node (ref "LED7") (pin "VDD") (pinfunction "VDD_VDD") (pintype "power_in"))
      (node (ref "LED8") (pin "VDD") (pinfunction "VDD_VDD") (pintype "power_in"))
      (node (ref "LED9") (pin "VDD") (pinfunction "VDD_VDD") (pintype "power_in"))
      (node (ref "LTC4412") (pin "6") (pinfunction "SENSE_6") (pintype "bidirectional"))
      (node (ref "PUSHPULL") (pin "1") (pinfunction "1OE_1") (pintype "bidirectional"))
      (node (ref "PUSHPULL") (pin "14") (pinfunction "VCC_14") (pintype "bidirectional"))
      (node (ref "PUSHPULL") (pin "4") (pinfunction "2OE_4") (pintype "bidirectional"))
      (node (ref "R2") (pin "2") (pinfunction "2_2") (pintype "passive"))
      (node (ref "T1") (pin "1") (pinfunction "S_1") (pintype "passive"))
      (node (ref "T1") (pin "2") (pinfunction "S_2") (pintype "passive"))
      (node (ref "T1") (pin "3") (pinfunction "S_3") (pintype "passive"))
      (node (ref "T2") (pin "1") (pinfunction "S_1") (pintype "passive"))
      (node (ref "T2") (pin "2") (pinfunction "S_2") (pintype "passive"))
      (node (ref "T2") (pin "3") (pinfunction "S_3") (pintype "passive"))
    )
    (net (code "3") (name "D+") (class "Default")
      (node (ref "C69") (pin "2") (pinfunction "2_2") (pintype "passive"))
      (node (ref "MCU") (pin "71") (pinfunction "PA12_71") (pintype "bidirectional"))
      (node (ref "R5") (pin "2") (pinfunction "2_2") (pintype "passive"))
      (node (ref "R6") (pin "1") (pinfunction "1_1") (pintype "passive"))
    )
    (net (code "4") (name "D-") (class "Default")
      (node (ref "C70") (pin "2") (pinfunction "2_2") (pintype "passive"))
      (node (ref "MCU") (pin "70") (pinfunction "PA11_70") (pintype "bidirectional"))
      (node (ref "R4") (pin "2") (pinfunction "2_2") (pintype "passive"))
    )
    (net (code "5") (name "DATA_IN_1_HIGH") (class "Default")
      (node (ref "PUSHPULL") (pin "11") (pinfunction "4Y_11") (pintype "bidirectional"))
      (node (ref "R1") (pin "1") (pinfunction "1_1") (pintype "passive"))
    )
    (net (code "6") (name "DATA_IN_1_LOW") (class "Default")
      (node (ref "MCU") (pin "39") (pinfunction "PE9_39") (pintype "bidirectional"))
      (node (ref "PUSHPULL") (pin "12") (pinfunction "4A_12") (pintype "bidirectional"))
    )
    (net (code "7") (name "DATA_IN_2_HIGH") (class "Default")
      (node (ref "PUSHPULL") (pin "8") (pinfunction "3Y_8") (pintype "bidirectional"))
      (node (ref "R3") (pin "1") (pinfunction "1_1") (pintype "passive"))
    )
    (net (code "8") (name "DATA_IN_2_LOW") (class "Default")
      (node (ref "MCU") (pin "41") (pinfunction "PE11_41") (pintype "bidirectional"))
      (node (ref "PUSHPULL") (pin "9") (pinfunction "3A_9") (pintype "bidirectional"))
    )
    (net (code "9") (name "GND") (class "Default")
      (node (ref "C1") (pin "2") (pinfunction "2_2") (pintype "passive"))
      (node (ref "C10") (pin "2") (pinfunction "2_2") (pintype "passive"))
      (node (ref "C11") (pin "2") (pinfunction "2_2") (pintype "passive"))
      (node (ref "C12") (pin "2") (pinfunction "2_2") (pintype "passive"))
      (node (ref "C13") (pin "2") (pinfunction "2_2") (pintype "passive"))
      (node (ref "C14") (pin "2") (pinfunction "2_2") (pintype "passive"))
      (node (ref "C15") (pin "2") (pinfunction "2_2") (pintype "passive"))
      (node (ref "C16") (pin "2") (pinfunction "2_2") (pintype "passive"))
      (node (ref "C17") (pin "2") (pinfunction "2_2") (pintype "passive"))
      (node (ref "C18") (pin "2") (pinfunction "2_2") (pintype "passive"))
      (node (ref "C19") (pin "2") (pinfunction "2_2") (pintype "passive"))
      (node (ref "C2") (pin "2") (pinfunction "2_2") (pintype "passive"))
      (node (ref "C20") (pin "2") (pinfunction "2_2") (pintype "passive"))
      (node (ref "C21") (pin "2") (pinfunction "2_2") (pintype "passive"))
      (node (ref "C22") (pin "2") (pinfunction "2_2") (pintype "passive"))
      (node (ref "C23") (pin "2") (pinfunction "2_2") (pintype "passive"))
      (node (ref "C24") (pin "2") (pinfunction "2_2") (pintype "passive"))
      (node (ref "C25") (pin "2") (pinfunction "2_2") (pintype "passive"))
      (node (ref "C26") (pin "2") (pinfunction "2_2") (pintype "passive"))
      (node (ref "C27") (pin "2") (pinfunction "2_2") (pintype "passive"))
      (node (ref "C28") (pin "2") (pinfunction "2_2") (pintype "passive"))
      (node (ref "C29") (pin "2") (pinfunction "2_2") (pintype "passive"))
      (node (ref "C3") (pin "2") (pinfunction "2_2") (pintype "passive"))
      (node (ref "C30") (pin "2") (pinfunction "2_2") (pintype "passive"))
      (node (ref "C31") (pin "2") (pinfunction "2_2") (pintype "passive"))
      (node (ref "C32") (pin "2") (pinfunction "2_2") (pintype "passive"))
      (node (ref "C33") (pin "2") (pinfunction "2_2") (pintype "passive"))
      (node (ref "C34") (pin "2") (pinfunction "2_2") (pintype "passive"))
      (node (ref "C35") (pin "2") (pinfunction "2_2") (pintype "passive"))
      (node (ref "C36") (pin "2") (pinfunction "2_2") (pintype "passive"))
      (node (ref "C37") (pin "2") (pinfunction "2_2") (pintype "passive"))
      (node (ref "C38") (pin "2") (pinfunction "2_2") (pintype "passive"))
      (node (ref "C39") (pin "2") (pinfunction "2_2") (pintype "passive"))
      (node (ref "C4") (pin "2") (pinfunction "2_2") (pintype "passive"))
      (node (ref "C40") (pin "2") (pinfunction "2_2") (pintype "passive"))
      (node (ref "C41") (pin "2") (pinfunction "2_2") (pintype "passive"))
      (node (ref "C42") (pin "2") (pinfunction "2_2") (pintype "passive"))
      (node (ref "C43") (pin "2") (pinfunction "2_2") (pintype "passive"))
      (node (ref "C44") (pin "2") (pinfunction "2_2") (pintype "passive"))
      (node (ref "C45") (pin "2") (pinfunction "2_2") (pintype "passive"))
      (node (ref "C46") (pin "2") (pinfunction "2_2") (pintype "passive"))
      (node (ref "C47") (pin "2") (pinfunction "2_2") (pintype "passive"))
      (node (ref "C48") (pin "2") (pinfunction "2_2") (pintype "passive"))
      (node (ref "C49") (pin "2") (pinfunction "2_2") (pintype "passive"))
      (node (ref "C5") (pin "2") (pinfunction "2_2") (pintype "passive"))
      (node (ref "C50") (pin "2") (pinfunction "2_2") (pintype "passive"))
      (node (ref "C51") (pin "2") (pinfunction "2_2") (pintype "passive"))
      (node (ref "C52") (pin "2") (pinfunction "2_2") (pintype "passive"))
      (node (ref "C53") (pin "2") (pinfunction "2_2") (pintype "passive"))
      (node (ref "C54") (pin "2") (pinfunction "2_2") (pintype "passive"))
      (node (ref "C55") (pin "2") (pinfunction "2_2") (pintype "passive"))
      (node (ref "C56") (pin "2") (pinfunction "2_2") (pintype "passive"))
      (node (ref "C57") (pin "2") (pinfunction "2_2") (pintype "passive"))
      (node (ref "C58") (pin "2") (pinfunction "2_2") (pintype "passive"))
      (node (ref "C59") (pin "2") (pinfunction "2_2") (pintype "passive"))
      (node (ref "C6") (pin "2") (pinfunction "2_2") (pintype "passive"))
      (node (ref "C60") (pin "2") (pinfunction "2_2") (pintype "passive"))
      (node (ref "C61") (pin "1") (pinfunction "1_1") (pintype "passive"))
      (node (ref "C62") (pin "2") (pinfunction "2_2") (pintype "passive"))
      (node (ref "C63") (pin "2") (pinfunction "2_2") (pintype "passive"))
      (node (ref "C64") (pin "2") (pinfunction "2_2") (pintype "passive"))
      (node (ref "C65") (pin "2") (pinfunction "2_2") (pintype "passive"))
      (node (ref "C66") (pin "2") (pinfunction "2_2") (pintype "passive"))
      (node (ref "C67") (pin "1") (pinfunction "1_1") (pintype "passive"))
      (node (ref "C68") (pin "1") (pinfunction "1_1") (pintype "passive"))
      (node (ref "C69") (pin "1") (pinfunction "1_1") (pintype "passive"))
      (node (ref "C7") (pin "2") (pinfunction "2_2") (pintype "passive"))
      (node (ref "C70") (pin "1") (pinfunction "1_1") (pintype "passive"))
      (node (ref "C71") (pin "2") (pinfunction "2_2") (pintype "passive"))
      (node (ref "C72") (pin "2") (pinfunction "2_2") (pintype "passive"))
      (node (ref "C73") (pin "2") (pinfunction "2_2") (pintype "passive"))
      (node (ref "C74") (pin "2") (pinfunction "2_2") (pintype "passive"))
      (node (ref "C75") (pin "2") (pinfunction "2_2") (pintype "passive"))
      (node (ref "C76") (pin "2") (pinfunction "2_2") (pintype "passive"))
      (node (ref "C77") (pin "2") (pinfunction "2_2") (pintype "passive"))
      (node (ref "C78") (pin "2") (pinfunction "2_2") (pintype "passive"))
      (node (ref "C79") (pin "2") (pinfunction "2_2") (pintype "passive"))
      (node (ref "C8") (pin "2") (pinfunction "2_2") (pintype "passive"))
      (node (ref "C80") (pin "2") (pinfunction "2_2") (pintype "passive"))
      (node (ref "C9") (pin "2") (pinfunction "2_2") (pintype "passive"))
      (node (ref "D1") (pin "2") (pinfunction "GND_2") (pintype "power_in"))
      (node (ref "JP1") (pin "10") (pinfunction "10_10") (pintype "passive"))
      (node (ref "JP1") (pin "12") (pinfunction "12_12") (pintype "passive"))
      (node (ref "JP1") (pin "14") (pinfunction "14_14") (pintype "passive"))
      (node (ref "JP1") (pin "16") (pinfunction "16_16") (pintype "passive"))
      (node (ref "JP1") (pin "18") (pinfunction "18_18") (pintype "passive"))
      (node (ref "JP1") (pin "20") (pinfunction "20_20") (pintype "passive"))
      (node (ref "JP1") (pin "4") (pinfunction "4_4") (pintype "passive"))
      (node (ref "JP1") (pin "6") (pinfunction "6_6") (pintype "passive"))
      (node (ref "JP1") (pin "8") (pinfunction "8_8") (pintype "passive"))
      (node (ref "K1") (pin "2") (pinfunction "2_2") (pintype "passive"))
      (node (ref "K1") (pin "3") (pinfunction "3_3") (pintype "passive"))
      (node (ref "LDO") (pin "2") (pinfunction "GND_2") (pintype "bidirectional"))
      (node (ref "LED1") (pin "VSS") (pinfunction "GND_VSS") (pintype "power_in"))
      (node (ref "LED10") (pin "VSS") (pinfunction "GND_VSS") (pintype "power_in"))
      (node (ref "LED11") (pin "VSS") (pinfunction "GND_VSS") (pintype "power_in"))
      (node (ref "LED12") (pin "VSS") (pinfunction "GND_VSS") (pintype "power_in"))
      (node (ref "LED13") (pin "VSS") (pinfunction "GND_VSS") (pintype "power_in"))
      (node (ref "LED14") (pin "VSS") (pinfunction "GND_VSS") (pintype "power_in"))
      (node (ref "LED15") (pin "VSS") (pinfunction "GND_VSS") (pintype "power_in"))
      (node (ref "LED16") (pin "VSS") (pinfunction "GND_VSS") (pintype "power_in"))
      (node (ref "LED17") (pin "VSS") (pinfunction "GND_VSS") (pintype "power_in"))
      (node (ref "LED18") (pin "VSS") (pinfunction "GND_VSS") (pintype "power_in"))
      (node (ref "LED19") (pin "VSS") (pinfunction "GND_VSS") (pintype "power_in"))
      (node (ref "LED2") (pin "VSS") (pinfunction "GND_VSS") (pintype "power_in"))
      (node (ref "LED20") (pin "VSS") (pinfunction "GND_VSS") (pintype "power_in"))
      (node (ref "LED21") (pin "VSS") (pinfunction "GND_VSS") (pintype "power_in"))
      (node (ref "LED22") (pin "VSS") (pinfunction "GND_VSS") (pintype "power_in"))
      (node (ref "LED23") (pin "VSS") (pinfunction "GND_VSS") (pintype "power_in"))
      (node (ref "LED24") (pin "VSS") (pinfunction "GND_VSS") (pintype "power_in"))
      (node (ref "LED25") (pin "VSS") (pinfunction "GND_VSS") (pintype "power_in"))
      (node (ref "LED26") (pin "VSS") (pinfunction "GND_VSS") (pintype "power_in"))
      (node (ref "LED27") (pin "VSS") (pinfunction "GND_VSS") (pintype "power_in"))
      (node (ref "LED28") (pin "VSS") (pinfunction "GND_VSS") (pintype "power_in"))
      (node (ref "LED29") (pin "VSS") (pinfunction "GND_VSS") (pintype "power_in"))
      (node (ref "LED3") (pin "VSS") (pinfunction "GND_VSS") (pintype "power_in"))
      (node (ref "LED30") (pin "VSS") (pinfunction "GND_VSS") (pintype "power_in"))
      (node (ref "LED31") (pin "VSS") (pinfunction "GND_VSS") (pintype "power_in"))
      (node (ref "LED32") (pin "VSS") (pinfunction "GND_VSS") (pintype "power_in"))
      (node (ref "LED33") (pin "VSS") (pinfunction "GND_VSS") (pintype "power_in"))
      (node (ref "LED34") (pin "VSS") (pinfunction "GND_VSS") (pintype "power_in"))
      (node (ref "LED35") (pin "VSS") (pinfunction "GND_VSS") (pintype "power_in"))
      (node (ref "LED36") (pin "VSS") (pinfunction "GND_VSS") (pintype "power_in"))
      (node (ref "LED37") (pin "VSS") (pinfunction "GND_VSS") (pintype "power_in"))
      (node (ref "LED38") (pin "VSS") (pinfunction "GND_VSS") (pintype "power_in"))
      (node (ref "LED39") (pin "VSS") (pinfunction "GND_VSS") (pintype "power_in"))
      (node (ref "LED4") (pin "VSS") (pinfunction "GND_VSS") (pintype "power_in"))
      (node (ref "LED40") (pin "VSS") (pinfunction "GND_VSS") (pintype "power_in"))
      (node (ref "LED41") (pin "VSS") (pinfunction "GND_VSS") (pintype "power_in"))
      (node (ref "LED42") (pin "VSS") (pinfunction "GND_VSS") (pintype "power_in"))
      (node (ref "LED43") (pin "VSS") (pinfunction "GND_VSS") (pintype "power_in"))
      (node (ref "LED44") (pin "VSS") (pinfunction "GND_VSS") (pintype "power_in"))
      (node (ref "LED45") (pin "VSS") (pinfunction "GND_VSS") (pintype "power_in"))
      (node (ref "LED46") (pin "VSS") (pinfunction "GND_VSS") (pintype "power_in"))
      (node (ref "LED47") (pin "VSS") (pinfunction "GND_VSS") (pintype "power_in"))
      (node (ref "LED48") (pin "VSS") (pinfunction "GND_VSS") (pintype "power_in"))
      (node (ref "LED49") (pin "VSS") (pinfunction "GND_VSS") (pintype "power_in"))
      (node (ref "LED5") (pin "VSS") (pinfunction "GND_VSS") (pintype "power_in"))
      (node (ref "LED50") (pin "VSS") (pinfunction "GND_VSS") (pintype "power_in"))
      (node (ref "LED51") (pin "VSS") (pinfunction "GND_VSS") (pintype "power_in"))
      (node (ref "LED52") (pin "VSS") (pinfunction "GND_VSS") (pintype "power_in"))
      (node (ref "LED53") (pin "VSS") (pinfunction "GND_VSS") (pintype "power_in"))
      (node (ref "LED54") (pin "VSS") (pinfunction "GND_VSS") (pintype "power_in"))
      (node (ref "LED55") (pin "VSS") (pinfunction "GND_VSS") (pintype "power_in"))
      (node (ref "LED56") (pin "VSS") (pinfunction "GND_VSS") (pintype "power_in"))
      (node (ref "LED57") (pin "VSS") (pinfunction "GND_VSS") (pintype "power_in"))
      (node (ref "LED58") (pin "VSS") (pinfunction "GND_VSS") (pintype "power_in"))
      (node (ref "LED59") (pin "VSS") (pinfunction "GND_VSS") (pintype "power_in"))
      (node (ref "LED6") (pin "VSS") (pinfunction "GND_VSS") (pintype "power_in"))
      (node (ref "LED60") (pin "VSS") (pinfunction "GND_VSS") (pintype "power_in"))
      (node (ref "LED7") (pin "VSS") (pinfunction "GND_VSS") (pintype "power_in"))
      (node (ref "LED8") (pin "VSS") (pinfunction "GND_VSS") (pintype "power_in"))
      (node (ref "LED9") (pin "VSS") (pinfunction "GND_VSS") (pintype "power_in"))
      (node (ref "LTC4412") (pin "2") (pinfunction "GND_2") (pintype "bidirectional"))
      (node (ref "LTC4412") (pin "3") (pinfunction "CTL_3") (pintype "bidirectional"))
      (node (ref "MCU") (pin "10") (pinfunction "VSS1_10") (pintype "power_in"))
      (node (ref "MCU") (pin "19") (pinfunction "VSSA_19") (pintype "power_in"))
      (node (ref "MCU") (pin "26") (pinfunction "VSS2_26") (pintype "power_in"))
      (node (ref "MCU") (pin "49") (pinfunction "VSS3_49") (pintype "power_in"))
      (node (ref "MCU") (pin "74") (pinfunction "VSS4_74") (pintype "power_in"))
      (node (ref "MCU") (pin "99") (pinfunction "VSS5_99") (pintype "power_in"))
      (node (ref "PUSHPULL") (pin "10") (pinfunction "3OE_10") (pintype "bidirectional"))
      (node (ref "PUSHPULL") (pin "13") (pinfunction "4OE_13") (pintype "bidirectional"))
      (node (ref "PUSHPULL") (pin "3") (pinfunction "1Y_3") (pintype "bidirectional"))
      (node (ref "PUSHPULL") (pin "6") (pinfunction "2Y_6") (pintype "bidirectional"))
      (node (ref "PUSHPULL") (pin "7") (pinfunction "GND_7") (pintype "bidirectional"))
      (node (ref "R6") (pin "2") (pinfunction "2_2") (pintype "passive"))
      (node (ref "R7") (pin "2") (pinfunction "2_2") (pintype "passive"))
      (node (ref "R8") (pin "2") (pinfunction "2_2") (pintype "passive"))
      (node (ref "R9") (pin "2") (pinfunction "2_2") (pintype "passive"))
      (node (ref "X1") (pin "GND") (pinfunction "GND_GND") (pintype "bidirectional"))
      (node (ref "X2") (pin "SHIELD@1") (pinfunction "SHIELD_SHIELD@1") (pintype "bidirectional"))
      (node (ref "X2") (pin "SHIELD@2") (pinfunction "SHIELD_SHIELD@2") (pintype "bidirectional"))
    )
    (net (code "10") (name "JTCK") (class "Default")
      (node (ref "JP1") (pin "9") (pinfunction "9_9") (pintype "passive"))
      (node (ref "MCU") (pin "76") (pinfunction "PA14_76") (pintype "bidirectional"))
    )
    (net (code "11") (name "JTDI") (class "Default")
      (node (ref "JP1") (pin "5") (pinfunction "5_5") (pintype "passive"))
      (node (ref "MCU") (pin "77") (pinfunction "PA15_77") (pintype "bidirectional"))
    )
    (net (code "12") (name "JTDO") (class "Default")
      (node (ref "JP1") (pin "13") (pinfunction "13_13") (pintype "passive"))
      (node (ref "MCU") (pin "89") (pinfunction "PB3_89") (pintype "bidirectional"))
    )
    (net (code "13") (name "JTMS") (class "Default")
      (node (ref "JP1") (pin "7") (pinfunction "7_7") (pintype "passive"))
      (node (ref "MCU") (pin "72") (pinfunction "PA13_72") (pintype "bidirectional"))
    )
    (net (code "14") (name "NJTRST") (class "Default")
      (node (ref "JP1") (pin "3") (pinfunction "3_3") (pintype "passive"))
      (node (ref "MCU") (pin "90") (pinfunction "PB4_90") (pintype "bidirectional"))
    )
    (net (code "15") (name "NRSTIN") (class "Default")
      (node (ref "JP1") (pin "15") (pinfunction "15_15") (pintype "passive"))
      (node (ref "MCU") (pin "14") (pinfunction "NRST_14") (pintype "bidirectional"))
    )
    (net (code "16") (name "Net-(0.5-I)") (class "Default")
      (node (ref "0.5") (pin "P$1") (pinfunction "I_P$1") (pintype "bidirectional"))
      (node (ref "D3") (pin "1") (pinfunction "C_1") (pintype "passive"))
    )
    (net (code "17") (name "Net-(4-I)") (class "Default")
      (node (ref "4") (pin "P$1") (pinfunction "I_P$1") (pintype "bidirectional"))
      (node (ref "K1") (pin "1") (pinfunction "1_1") (pintype "passive"))
    )
    (net (code "18") (name "Net-(4-O)") (class "Default")
      (node (ref "4") (pin "P$2") (pinfunction "O_P$2") (pintype "bidirectional"))
      (node (ref "C80") (pin "1") (pinfunction "1_1") (pintype "passive"))
      (node (ref "LTC4412") (pin "1") (pinfunction "VIN_1") (pintype "bidirectional"))
      (node (ref "T2") (pin "5") (pinfunction "D_5") (pintype "passive"))
      (node (ref "T2") (pin "6") (pinfunction "D_6") (pintype "passive"))
      (node (ref "T2") (pin "7") (pinfunction "D_7") (pintype "passive"))
      (node (ref "T2") (pin "8") (pinfunction "D_8") (pintype "passive"))
    )
    (net (code "19") (name "Net-(D1-2)") (class "Default")
      (node (ref "D1") (pin "3") (pinfunction "2_3") (pintype "passive"))
      (node (ref "L1") (pin "3") (pinfunction "2_3") (pintype "passive"))
    )
    (net (code "20") (name "Net-(D1-3)") (class "Default")
      (node (ref "D1") (pin "4") (pinfunction "3_4") (pintype "passive"))
      (node (ref "R5") (pin "1") (pinfunction "1_1") (pintype "passive"))
    )
    (net (code "21") (name "Net-(D1-4)") (class "Default")
      (node (ref "D1") (pin "6") (pinfunction "4_6") (pintype "passive"))
      (node (ref "R4") (pin "1") (pinfunction "1_1") (pintype "passive"))
    )
    (net (code "22") (name "Net-(JP1-Pad11)") (class "Default")
      (node (ref "JP1") (pin "11") (pinfunction "11_11") (pintype "passive"))
      (node (ref "R9") (pin "1") (pinfunction "1_1") (pintype "passive"))
    )
    (net (code "23") (name "Net-(JP1-Pad17)") (class "Default")
      (node (ref "JP1") (pin "17") (pinfunction "17_17") (pintype "passive"))
      (node (ref "R8") (pin "1") (pinfunction "1_1") (pintype "passive"))
    )
    (net (code "24") (name "Net-(JP1-Pad19)") (class "Default")
      (node (ref "JP1") (pin "19") (pinfunction "19_19") (pintype "passive"))
      (node (ref "R7") (pin "1") (pinfunction "1_1") (pintype "passive"))
    )
    (net (code "25") (name "Net-(L1-1)") (class "Default")
      (node (ref "L1") (pin "4") (pinfunction "1_4") (pintype "passive"))
      (node (ref "X1") (pin "D+") (pinfunction "D+_D+") (pintype "bidirectional"))
    )
    (net (code "26") (name "Net-(L1-3)") (class "Default")
      (node (ref "D1") (pin "1") (pinfunction "1_1") (pintype "passive"))
      (node (ref "L1") (pin "2") (pinfunction "3_2") (pintype "passive"))
    )
    (net (code "27") (name "Net-(L1-4)") (class "Default")
      (node (ref "L1") (pin "1") (pinfunction "4_1") (pintype "passive"))
      (node (ref "X1") (pin "D-") (pinfunction "D-_D-") (pintype "bidirectional"))
    )
    (net (code "28") (name "Net-(LED1-DI)") (class "Default")
      (node (ref "LED1") (pin "DIN") (pinfunction "DI_DIN") (pintype "input"))
      (node (ref "LED30") (pin "DOUT") (pinfunction "DO_DOUT") (pintype "output"))
    )
    (net (code "29") (name "Net-(LED1-DO)") (class "Default")
      (node (ref "LED1") (pin "DOUT") (pinfunction "DO_DOUT") (pintype "output"))
      (node (ref "LED2") (pin "DIN") (pinfunction "DI_DIN") (pintype "input"))
    )
    (net (code "30") (name "Net-(LED2-DO)") (class "Default")
      (node (ref "LED2") (pin "DOUT") (pinfunction "DO_DOUT") (pintype "output"))
      (node (ref "LED3") (pin "DIN") (pinfunction "DI_DIN") (pintype "input"))
    )
    (net (code "31") (name "Net-(LED3-DO)") (class "Default")
      (node (ref "LED3") (pin "DOUT") (pinfunction "DO_DOUT") (pintype "output"))
      (node (ref "LED4") (pin "DIN") (pinfunction "DI_DIN") (pintype "input"))
    )
    (net (code "32") (name "Net-(LED4-DO)") (class "Default")
      (node (ref "LED4") (pin "DOUT") (pinfunction "DO_DOUT") (pintype "output"))
      (node (ref "LED5") (pin "DIN") (pinfunction "DI_DIN") (pintype "input"))
    )
    (net (code "33") (name "Net-(LED5-DO)") (class "Default")
      (node (ref "LED5") (pin "DOUT") (pinfunction "DO_DOUT") (pintype "output"))
      (node (ref "LED6") (pin "DIN") (pinfunction "DI_DIN") (pintype "input"))
    )
    (net (code "34") (name "Net-(LED7-DI)") (class "Default")
      (node (ref "LED7") (pin "DIN") (pinfunction "DI_DIN") (pintype "input"))
      (node (ref "R3") (pin "2") (pinfunction "2_2") (pintype "passive"))
    )
    (net (code "35") (name "Net-(LED7-DO)") (class "Default")
      (node (ref "LED7") (pin "DOUT") (pinfunction "DO_DOUT") (pintype "output"))
      (node (ref "LED8") (pin "DIN") (pinfunction "DI_DIN") (pintype "input"))
    )
    (net (code "36") (name "Net-(LED8-DO)") (class "Default")
      (node (ref "LED8") (pin "DOUT") (pinfunction "DO_DOUT") (pintype "output"))
      (node (ref "LED9") (pin "DIN") (pinfunction "DI_DIN") (pintype "input"))
    )
    (net (code "37") (name "Net-(LED10-DI)") (class "Default")
      (node (ref "LED10") (pin "DIN") (pinfunction "DI_DIN") (pintype "input"))
      (node (ref "LED9") (pin "DOUT") (pinfunction "DO_DOUT") (pintype "output"))
    )
    (net (code "38") (name "Net-(LED10-DO)") (class "Default")
      (node (ref "LED10") (pin "DOUT") (pinfunction "DO_DOUT") (pintype "output"))
      (node (ref "LED11") (pin "DIN") (pinfunction "DI_DIN") (pintype "input"))
    )
    (net (code "39") (name "Net-(LED11-DO)") (class "Default")
      (node (ref "LED11") (pin "DOUT") (pinfunction "DO_DOUT") (pintype "output"))
      (node (ref "LED12") (pin "DIN") (pinfunction "DI_DIN") (pintype "input"))
    )
    (net (code "40") (name "Net-(LED12-DO)") (class "Default")
      (node (ref "LED12") (pin "DOUT") (pinfunction "DO_DOUT") (pintype "output"))
      (node (ref "LED13") (pin "DIN") (pinfunction "DI_DIN") (pintype "input"))
    )
    (net (code "41") (name "Net-(LED13-DO)") (class "Default")
      (node (ref "LED13") (pin "DOUT") (pinfunction "DO_DOUT") (pintype "output"))
      (node (ref "LED14") (pin "DIN") (pinfunction "DI_DIN") (pintype "input"))
    )
    (net (code "42") (name "Net-(LED14-DO)") (class "Default")
      (node (ref "LED14") (pin "DOUT") (pinfunction "DO_DOUT") (pintype "output"))
      (node (ref "LED15") (pin "DIN") (pinfunction "DI_DIN") (pintype "input"))
    )
    (net (code "43") (name "Net-(LED15-DO)") (class "Default")
      (node (ref "LED15") (pin "DOUT") (pinfunction "DO_DOUT") (pintype "output"))
      (node (ref "LED16") (pin "DIN") (pinfunction "DI_DIN") (pintype "input"))
    )
    (net (code "44") (name "Net-(LED16-DO)") (class "Default")
      (node (ref "LED16") (pin "DOUT") (pinfunction "DO_DOUT") (pintype "output"))
      (node (ref "LED17") (pin "DIN") (pinfunction "DI_DIN") (pintype "input"))
    )
    (net (code "45") (name "Net-(LED17-DO)") (class "Default")
      (node (ref "LED17") (pin "DOUT") (pinfunction "DO_DOUT") (pintype "output"))
      (node (ref "LED18") (pin "DIN") (pinfunction "DI_DIN") (pintype "input"))
    )
    (net (code "46") (name "Net-(LED18-DO)") (class "Default")
      (node (ref "LED18") (pin "DOUT") (pinfunction "DO_DOUT") (pintype "output"))
      (node (ref "LED19") (pin "DIN") (pinfunction "DI_DIN") (pintype "input"))
    )
    (net (code "47") (name "Net-(LED19-DO)") (class "Default")
      (node (ref "LED19") (pin "DOUT") (pinfunction "DO_DOUT") (pintype "output"))
      (node (ref "LED20") (pin "DIN") (pinfunction "DI_DIN") (pintype "input"))
    )
    (net (code "48") (name "Net-(LED20-DO)") (class "Default")
      (node (ref "LED20") (pin "DOUT") (pinfunction "DO_DOUT") (pintype "output"))
      (node (ref "LED21") (pin "DIN") (pinfunction "DI_DIN") (pintype "input"))
    )
    (net (code "49") (name "Net-(LED21-DO)") (class "Default")
      (node (ref "LED21") (pin "DOUT") (pinfunction "DO_DOUT") (pintype "output"))
      (node (ref "LED22") (pin "DIN") (pinfunction "DI_DIN") (pintype "input"))
    )
    (net (code "50") (name "Net-(LED22-DO)") (class "Default")
      (node (ref "LED22") (pin "DOUT") (pinfunction "DO_DOUT") (pintype "output"))
      (node (ref "LED23") (pin "DIN") (pinfunction "DI_DIN") (pintype "input"))
    )
    (net (code "51") (name "Net-(LED23-DO)") (class "Default")
      (node (ref "LED23") (pin "DOUT") (pinfunction "DO_DOUT") (pintype "output"))
      (node (ref "LED24") (pin "DIN") (pinfunction "DI_DIN") (pintype "input"))
    )
    (net (code "52") (name "Net-(LED24-DO)") (class "Default")
      (node (ref "LED24") (pin "DOUT") (pinfunction "DO_DOUT") (pintype "output"))
      (node (ref "LED25") (pin "DIN") (pinfunction "DI_DIN") (pintype "input"))
    )
    (net (code "53") (name "Net-(LED25-DO)") (class "Default")
      (node (ref "LED25") (pin "DOUT") (pinfunction "DO_DOUT") (pintype "output"))
      (node (ref "LED26") (pin "DIN") (pinfunction "DI_DIN") (pintype "input"))
    )
    (net (code "54") (name "Net-(LED26-DO)") (class "Default")
      (node (ref "LED26") (pin "DOUT") (pinfunction "DO_DOUT") (pintype "output"))
      (node (ref "LED27") (pin "DIN") (pinfunction "DI_DIN") (pintype "input"))
    )
    (net (code "55") (name "Net-(LED27-DO)") (class "Default")
      (node (ref "LED27") (pin "DOUT") (pinfunction "DO_DOUT") (pintype "output"))
      (node (ref "LED28") (pin "DIN") (pinfunction "DI_DIN") (pintype "input"))
    )
    (net (code "56") (name "Net-(LED28-DO)") (class "Default")
      (node (ref "LED28") (pin "DOUT") (pinfunction "DO_DOUT") (pintype "output"))
      (node (ref "LED29") (pin "DIN") (pinfunction "DI_DIN") (pintype "input"))
    )
    (net (code "57") (name "Net-(LED29-DO)") (class "Default")
      (node (ref "LED29") (pin "DOUT") (pinfunction "DO_DOUT") (pintype "output"))
      (node (ref "LED30") (pin "DIN") (pinfunction "DI_DIN") (pintype "input"))
    )
    (net (code "58") (name "Net-(LED31-DI)") (class "Default")
      (node (ref "LED31") (pin "DIN") (pinfunction "DI_DIN") (pintype "input"))
      (node (ref "LED60") (pin "DOUT") (pinfunction "DO_DOUT") (pintype "output"))
    )
    (net (code "59") (name "Net-(LED31-DO)") (class "Default")
      (node (ref "LED31") (pin "DOUT") (pinfunction "DO_DOUT") (pintype "output"))
      (node (ref "LED32") (pin "DIN") (pinfunction "DI_DIN") (pintype "input"))
    )
    (net (code "60") (name "Net-(LED32-DO)") (class "Default")
      (node (ref "LED32") (pin "DOUT") (pinfunction "DO_DOUT") (pintype "output"))
      (node (ref "LED33") (pin "DIN") (pinfunction "DI_DIN") (pintype "input"))
    )
    (net (code "61") (name "Net-(LED33-DO)") (class "Default")
      (node (ref "LED33") (pin "DOUT") (pinfunction "DO_DOUT") (pintype "output"))
      (node (ref "LED34") (pin "DIN") (pinfunction "DI_DIN") (pintype "input"))
    )
    (net (code "62") (name "Net-(LED34-DO)") (class "Default")
      (node (ref "LED34") (pin "DOUT") (pinfunction "DO_DOUT") (pintype "output"))
      (node (ref "LED35") (pin "DIN") (pinfunction "DI_DIN") (pintype "input"))
    )
    (net (code "63") (name "Net-(LED35-DO)") (class "Default")
      (node (ref "LED35") (pin "DOUT") (pinfunction "DO_DOUT") (pintype "output"))
      (node (ref "LED36") (pin "DIN") (pinfunction "DI_DIN") (pintype "input"))
    )
    (net (code "64") (name "Net-(LED36-DO)") (class "Default")
      (node (ref "LED36") (pin "DOUT") (pinfunction "DO_DOUT") (pintype "output"))
      (node (ref "LED37") (pin "DIN") (pinfunction "DI_DIN") (pintype "input"))
    )
    (net (code "65") (name "Net-(LED38-DI)") (class "Default")
      (node (ref "LED38") (pin "DIN") (pinfunction "DI_DIN") (pintype "input"))
      (node (ref "R1") (pin "2") (pinfunction "2_2") (pintype "passive"))
    )
    (net (code "66") (name "Net-(LED38-DO)") (class "Default")
      (node (ref "LED38") (pin "DOUT") (pinfunction "DO_DOUT") (pintype "output"))
      (node (ref "LED39") (pin "DIN") (pinfunction "DI_DIN") (pintype "input"))
    )
    (net (code "67") (name "Net-(LED39-DO)") (class "Default")
      (node (ref "LED39") (pin "DOUT") (pinfunction "DO_DOUT") (pintype "output"))
      (node (ref "LED40") (pin "DIN") (pinfunction "DI_DIN") (pintype "input"))
    )
    (net (code "68") (name "Net-(LED40-DO)") (class "Default")
      (node (ref "LED40") (pin "DOUT") (pinfunction "DO_DOUT") (pintype "output"))
      (node (ref "LED41") (pin "DIN") (pinfunction "DI_DIN") (pintype "input"))
    )
    (net (code "69") (name "Net-(LED41-DO)") (class "Default")
      (node (ref "LED41") (pin "DOUT") (pinfunction "DO_DOUT") (pintype "output"))
      (node (ref "LED42") (pin "DIN") (pinfunction "DI_DIN") (pintype "input"))
    )
    (net (code "70") (name "Net-(LED42-DO)") (class "Default")
      (node (ref "LED42") (pin "DOUT") (pinfunction "DO_DOUT") (pintype "output"))
      (node (ref "LED43") (pin "DIN") (pinfunction "DI_DIN") (pintype "input"))
    )
    (net (code "71") (name "Net-(LED43-DO)") (class "Default")
      (node (ref "LED43") (pin "DOUT") (pinfunction "DO_DOUT") (pintype "output"))
      (node (ref "LED44") (pin "DIN") (pinfunction "DI_DIN") (pintype "input"))
    )
    (net (code "72") (name "Net-(LED44-DO)") (class "Default")
      (node (ref "LED44") (pin "DOUT") (pinfunction "DO_DOUT") (pintype "output"))
      (node (ref "LED45") (pin "DIN") (pinfunction "DI_DIN") (pintype "input"))
    )
    (net (code "73") (name "Net-(LED45-DO)") (class "Default")
      (node (ref "LED45") (pin "DOUT") (pinfunction "DO_DOUT") (pintype "output"))
      (node (ref "LED46") (pin "DIN") (pinfunction "DI_DIN") (pintype "input"))
    )
    (net (code "74") (name "Net-(LED46-DO)") (class "Default")
      (node (ref "LED46") (pin "DOUT") (pinfunction "DO_DOUT") (pintype "output"))
      (node (ref "LED47") (pin "DIN") (pinfunction "DI_DIN") (pintype "input"))
    )
    (net (code "75") (name "Net-(LED47-DO)") (class "Default")
      (node (ref "LED47") (pin "DOUT") (pinfunction "DO_DOUT") (pintype "output"))
      (node (ref "LED48") (pin "DIN") (pinfunction "DI_DIN") (pintype "input"))
    )
    (net (code "76") (name "Net-(LED48-DO)") (class "Default")
      (node (ref "LED48") (pin "DOUT") (pinfunction "DO_DOUT") (pintype "output"))
      (node (ref "LED49") (pin "DIN") (pinfunction "DI_DIN") (pintype "input"))
    )
    (net (code "77") (name "Net-(LED49-DO)") (class "Default")
      (node (ref "LED49") (pin "DOUT") (pinfunction "DO_DOUT") (pintype "output"))
      (node (ref "LED50") (pin "DIN") (pinfunction "DI_DIN") (pintype "input"))
    )
    (net (code "78") (name "Net-(LED50-DO)") (class "Default")
      (node (ref "LED50") (pin "DOUT") (pinfunction "DO_DOUT") (pintype "output"))
      (node (ref "LED51") (pin "DIN") (pinfunction "DI_DIN") (pintype "input"))
    )
    (net (code "79") (name "Net-(LED51-DO)") (class "Default")
      (node (ref "LED51") (pin "DOUT") (pinfunction "DO_DOUT") (pintype "output"))
      (node (ref "LED52") (pin "DIN") (pinfunction "DI_DIN") (pintype "input"))
    )
    (net (code "80") (name "Net-(LED52-DO)") (class "Default")
      (node (ref "LED52") (pin "DOUT") (pinfunction "DO_DOUT") (pintype "output"))
      (node (ref "LED53") (pin "DIN") (pinfunction "DI_DIN") (pintype "input"))
    )
    (net (code "81") (name "Net-(LED53-DO)") (class "Default")
      (node (ref "LED53") (pin "DOUT") (pinfunction "DO_DOUT") (pintype "output"))
      (node (ref "LED54") (pin "DIN") (pinfunction "DI_DIN") (pintype "input"))
    )
    (net (code "82") (name "Net-(LED54-DO)") (class "Default")
      (node (ref "LED54") (pin "DOUT") (pinfunction "DO_DOUT") (pintype "output"))
      (node (ref "LED55") (pin "DIN") (pinfunction "DI_DIN") (pintype "input"))
    )
    (net (code "83") (name "Net-(LED55-DO)") (class "Default")
      (node (ref "LED55") (pin "DOUT") (pinfunction "DO_DOUT") (pintype "output"))
      (node (ref "LED56") (pin "DIN") (pinfunction "DI_DIN") (pintype "input"))
    )
    (net (code "84") (name "Net-(LED56-DO)") (class "Default")
      (node (ref "LED56") (pin "DOUT") (pinfunction "DO_DOUT") (pintype "output"))
      (node (ref "LED57") (pin "DIN") (pinfunction "DI_DIN") (pintype "input"))
    )
    (net (code "85") (name "Net-(LED57-DO)") (class "Default")
      (node (ref "LED57") (pin "DOUT") (pinfunction "DO_DOUT") (pintype "output"))
      (node (ref "LED58") (pin "DIN") (pinfunction "DI_DIN") (pintype "input"))
    )
    (net (code "86") (name "Net-(LED58-DO)") (class "Default")
      (node (ref "LED58") (pin "DOUT") (pinfunction "DO_DOUT") (pintype "output"))
      (node (ref "LED59") (pin "DIN") (pinfunction "DI_DIN") (pintype "input"))
    )
    (net (code "87") (name "Net-(LED59-DO)") (class "Default")
      (node (ref "LED59") (pin "DOUT") (pinfunction "DO_DOUT") (pintype "output"))
      (node (ref "LED60") (pin "DIN") (pinfunction "DI_DIN") (pintype "input"))
    )
    (net (code "88") (name "Net-(LTC4412-GATE)") (class "Default")
      (node (ref "LTC4412") (pin "5") (pinfunction "GATE_5") (pintype "bidirectional"))
      (node (ref "T2") (pin "4") (pinfunction "G_4") (pintype "passive"))
    )
    (net (code "89") (name "Net-(MCU-VCAP1)") (class "Default")
      (node (ref "C77") (pin "1") (pinfunction "1_1") (pintype "passive"))
      (node (ref "MCU") (pin "48") (pinfunction "VCAP1_48") (pintype "bidirectional"))
    )
    (net (code "90") (name "Net-(MCU-VCAP2)") (class "Default")
      (node (ref "C76") (pin "1") (pinfunction "1_1") (pintype "passive"))
      (node (ref "MCU") (pin "73") (pinfunction "VCAP2_73") (pintype "bidirectional"))
    )
    (net (code "91") (name "Net-(U$1-Pad1)") (class "Default")
      (node (ref "U$1") (pin "1") (pinfunction "1_1") (pintype "bidirectional"))
      (node (ref "X2") (pin "1") (pinfunction "1_1") (pintype "bidirectional"))
    )
    (net (code "92") (name "Net-(U$1-Pad2)") (class "Default")
      (node (ref "U$1") (pin "2") (pinfunction "2_2") (pintype "bidirectional"))
      (node (ref "X2") (pin "2") (pinfunction "2_2") (pintype "bidirectional"))
    )
    (net (code "93") (name "Net-(U$1-Pad3)") (class "Default")
      (node (ref "U$1") (pin "3") (pinfunction "3_3") (pintype "bidirectional"))
      (node (ref "X2") (pin "3") (pinfunction "3_3") (pintype "bidirectional"))
    )
    (net (code "94") (name "Net-(U$1-Pad4)") (class "Default")
      (node (ref "U$1") (pin "4") (pinfunction "4_4") (pintype "bidirectional"))
      (node (ref "X2") (pin "4") (pinfunction "4_4") (pintype "bidirectional"))
    )
    (net (code "95") (name "Net-(U$1-Pad5)") (class "Default")
      (node (ref "U$1") (pin "5") (pinfunction "5_5") (pintype "bidirectional"))
      (node (ref "X2") (pin "5") (pinfunction "5_5") (pintype "bidirectional"))
    )
    (net (code "96") (name "Net-(U$1-Pad6)") (class "Default")
      (node (ref "U$1") (pin "6") (pinfunction "6_6") (pintype "bidirectional"))
      (node (ref "X2") (pin "6") (pinfunction "6_6") (pintype "bidirectional"))
    )
    (net (code "97") (name "Net-(U$1-Pad7)") (class "Default")
      (node (ref "U$1") (pin "7") (pinfunction "7_7") (pintype "bidirectional"))
      (node (ref "X2") (pin "7") (pinfunction "7_7") (pintype "bidirectional"))
    )
    (net (code "98") (name "Net-(U$1-Pad8)") (class "Default")
      (node (ref "U$1") (pin "8") (pinfunction "8_8") (pintype "bidirectional"))
      (node (ref "X2") (pin "8") (pinfunction "8_8") (pintype "bidirectional"))
    )
    (net (code "99") (name "OSC_IN") (class "Default")
      (node (ref "C74") (pin "1") (pinfunction "1_1") (pintype "passive"))
      (node (ref "MCU") (pin "12") (pinfunction "PH0-OSC_IN_12") (pintype "bidirectional"))
      (node (ref "Q1_24MHZ") (pin "1") (pinfunction "1_1") (pintype "passive"))
    )
    (net (code "100") (name "OSC_OUT") (class "Default")
      (node (ref "C75") (pin "1") (pinfunction "1_1") (pintype "passive"))
      (node (ref "MCU") (pin "13") (pinfunction "PH1-OSC_OUT_13") (pintype "bidirectional"))
      (node (ref "Q1_24MHZ") (pin "2") (pinfunction "2_2") (pintype "passive"))
    )
    (net (code "101") (name "PM_STATUS") (class "Default")
      (node (ref "LTC4412") (pin "4") (pinfunction "STAT_4") (pintype "bidirectional"))
      (node (ref "MCU") (pin "23") (pinfunction "PA1_23") (pintype "bidirectional"))
      (node (ref "R2") (pin "1") (pinfunction "1_1") (pintype "passive"))
      (node (ref "T1") (pin "4") (pinfunction "G_4") (pintype "passive"))
    )
    (net (code "102") (name "VBUS") (class "Default")
      (node (ref "C67") (pin "2") (pinfunction "2_2") (pintype "passive"))
      (node (ref "D3") (pin "3") (pinfunction "A_3") (pintype "passive"))
      (node (ref "X1") (pin "VBUS") (pinfunction "VBUS_VBUS") (pintype "bidirectional"))
    )
    (net (code "103") (name "VBUS_S") (class "Default")
      (node (ref "0.5") (pin "P$2") (pinfunction "O_P$2") (pintype "bidirectional"))
      (node (ref "C68") (pin "2") (pinfunction "2_2") (pintype "passive"))
      (node (ref "D1") (pin "5") (pinfunction "VDD_5") (pintype "power_in"))
      (node (ref "T1") (pin "5") (pinfunction "D_5") (pintype "passive"))
      (node (ref "T1") (pin "6") (pinfunction "D_6") (pintype "passive"))
      (node (ref "T1") (pin "7") (pinfunction "D_7") (pintype "passive"))
      (node (ref "T1") (pin "8") (pinfunction "D_8") (pintype "passive"))
    )
    (net (code "104") (name "unconnected-(LDO-NR-Pad4)") (class "Default")
      (node (ref "LDO") (pin "4") (pinfunction "NR_4") (pintype "bidirectional"))
    )
    (net (code "105") (name "unconnected-(LED6-DO-PadDOUT)") (class "Default")
      (node (ref "LED6") (pin "DOUT") (pinfunction "DO_DOUT") (pintype "output"))
    )
    (net (code "106") (name "unconnected-(LED37-DO-PadDOUT)") (class "Default")
      (node (ref "LED37") (pin "DOUT") (pinfunction "DO_DOUT") (pintype "output"))
    )
    (net (code "107") (name "unconnected-(MCU-BOOT0-Pad94)") (class "Default")
      (node (ref "MCU") (pin "94") (pinfunction "BOOT0_94") (pintype "bidirectional"))
    )
    (net (code "108") (name "unconnected-(MCU-PA0-WKUP-Pad22)") (class "Default")
      (node (ref "MCU") (pin "22") (pinfunction "PA0-WKUP_22") (pintype "bidirectional"))
    )
    (net (code "109") (name "unconnected-(MCU-PA2-Pad24)") (class "Default")
      (node (ref "MCU") (pin "24") (pinfunction "PA2_24") (pintype "bidirectional"))
    )
    (net (code "110") (name "unconnected-(MCU-PA3-Pad25)") (class "Default")
      (node (ref "MCU") (pin "25") (pinfunction "PA3_25") (pintype "bidirectional"))
    )
    (net (code "111") (name "unconnected-(MCU-PA4-Pad28)") (class "Default")
      (node (ref "MCU") (pin "28") (pinfunction "PA4_28") (pintype "bidirectional"))
    )
    (net (code "112") (name "unconnected-(MCU-PA5-Pad29)") (class "Default")
      (node (ref "MCU") (pin "29") (pinfunction "PA5_29") (pintype "bidirectional"))
    )
    (net (code "113") (name "unconnected-(MCU-PA6-Pad30)") (class "Default")
      (node (ref "MCU") (pin "30") (pinfunction "PA6_30") (pintype "bidirectional"))
    )
    (net (code "114") (name "unconnected-(MCU-PA7-Pad31)") (class "Default")
      (node (ref "MCU") (pin "31") (pinfunction "PA7_31") (pintype "bidirectional"))
    )
    (net (code "115") (name "unconnected-(MCU-PA8-Pad67)") (class "Default")
      (node (ref "MCU") (pin "67") (pinfunction "PA8_67") (pintype "bidirectional"))
    )
    (net (code "116") (name "unconnected-(MCU-PA9-Pad68)") (class "Default")
      (node (ref "MCU") (pin "68") (pinfunction "PA9_68") (pintype "bidirectional"))
    )
    (net (code "117") (name "unconnected-(MCU-PA10-Pad69)") (class "Default")
      (node (ref "MCU") (pin "69") (pinfunction "PA10_69") (pintype "bidirectional"))
    )
    (net (code "118") (name "unconnected-(MCU-PB0-Pad34)") (class "Default")
      (node (ref "MCU") (pin "34") (pinfunction "PB0_34") (pintype "bidirectional"))
    )
    (net (code "119") (name "unconnected-(MCU-PB1-Pad35)") (class "Default")
      (node (ref "MCU") (pin "35") (pinfunction "PB1_35") (pintype "bidirectional"))
    )
    (net (code "120") (name "unconnected-(MCU-PB2-Pad36)") (class "Default")
      (node (ref "MCU") (pin "36") (pinfunction "PB2_36") (pintype "bidirectional"))
    )
    (net (code "121") (name "unconnected-(MCU-PB5-Pad91)") (class "Default")
      (node (ref "MCU") (pin "91") (pinfunction "PB5_91") (pintype "bidirectional"))
    )
    (net (code "122") (name "unconnected-(MCU-PB6-Pad92)") (class "Default")
      (node (ref "MCU") (pin "92") (pinfunction "PB6_92") (pintype "bidirectional"))
    )
    (net (code "123") (name "unconnected-(MCU-PB7-Pad93)") (class "Default")
      (node (ref "MCU") (pin "93") (pinfunction "PB7_93") (pintype "bidirectional"))
    )
    (net (code "124") (name "unconnected-(MCU-PB8-Pad95)") (class "Default")
      (node (ref "MCU") (pin "95") (pinfunction "PB8_95") (pintype "bidirectional"))
    )
    (net (code "125") (name "unconnected-(MCU-PB9-Pad96)") (class "Default")
      (node (ref "MCU") (pin "96") (pinfunction "PB9_96") (pintype "bidirectional"))
    )
    (net (code "126") (name "unconnected-(MCU-PB10-Pad46)") (class "Default")
      (node (ref "MCU") (pin "46") (pinfunction "PB10_46") (pintype "bidirectional"))
    )
    (net (code "127") (name "unconnected-(MCU-PB11-Pad47)") (class "Default")
      (node (ref "MCU") (pin "47") (pinfunction "PB11_47") (pintype "bidirectional"))
    )
    (net (code "128") (name "unconnected-(MCU-PB12-Pad51)") (class "Default")
      (node (ref "MCU") (pin "51") (pinfunction "PB12_51") (pintype "bidirectional"))
    )
    (net (code "129") (name "unconnected-(MCU-PB13-Pad52)") (class "Default")
      (node (ref "MCU") (pin "52") (pinfunction "PB13_52") (pintype "bidirectional"))
    )
    (net (code "130") (name "unconnected-(MCU-PB14-Pad53)") (class "Default")
      (node (ref "MCU") (pin "53") (pinfunction "PB14_53") (pintype "bidirectional"))
    )
    (net (code "131") (name "unconnected-(MCU-PB15-Pad54)") (class "Default")
      (node (ref "MCU") (pin "54") (pinfunction "PB15_54") (pintype "bidirectional"))
    )
    (net (code "132") (name "unconnected-(MCU-PC0-Pad15)") (class "Default")
      (node (ref "MCU") (pin "15") (pinfunction "PC0_15") (pintype "bidirectional"))
    )
    (net (code "133") (name "unconnected-(MCU-PC1-Pad16)") (class "Default")
      (node (ref "MCU") (pin "16") (pinfunction "PC1_16") (pintype "bidirectional"))
    )
    (net (code "134") (name "unconnected-(MCU-PC2-Pad17)") (class "Default")
      (node (ref "MCU") (pin "17") (pinfunction "PC2_17") (pintype "bidirectional"))
    )
    (net (code "135") (name "unconnected-(MCU-PC3-Pad18)") (class "Default")
      (node (ref "MCU") (pin "18") (pinfunction "PC3_18") (pintype "bidirectional"))
    )
    (net (code "136") (name "unconnected-(MCU-PC4-Pad32)") (class "Default")
      (node (ref "MCU") (pin "32") (pinfunction "PC4_32") (pintype "bidirectional"))
    )
    (net (code "137") (name "unconnected-(MCU-PC5-Pad33)") (class "Default")
      (node (ref "MCU") (pin "33") (pinfunction "PC5_33") (pintype "bidirectional"))
    )
    (net (code "138") (name "unconnected-(MCU-PC6-Pad63)") (class "Default")
      (node (ref "MCU") (pin "63") (pinfunction "PC6_63") (pintype "bidirectional"))
    )
    (net (code "139") (name "unconnected-(MCU-PC7-Pad64)") (class "Default")
      (node (ref "MCU") (pin "64") (pinfunction "PC7_64") (pintype "bidirectional"))
    )
    (net (code "140") (name "unconnected-(MCU-PC8-Pad65)") (class "Default")
      (node (ref "MCU") (pin "65") (pinfunction "PC8_65") (pintype "bidirectional"))
    )
    (net (code "141") (name "unconnected-(MCU-PC9-Pad66)") (class "Default")
      (node (ref "MCU") (pin "66") (pinfunction "PC9_66") (pintype "bidirectional"))
    )
    (net (code "142") (name "unconnected-(MCU-PC10-Pad78)") (class "Default")
      (node (ref "MCU") (pin "78") (pinfunction "PC10_78") (pintype "bidirectional"))
    )
    (net (code "143") (name "unconnected-(MCU-PC11-Pad79)") (class "Default")
      (node (ref "MCU") (pin "79") (pinfunction "PC11_79") (pintype "bidirectional"))
    )
    (net (code "144") (name "unconnected-(MCU-PC12-Pad80)") (class "Default")
      (node (ref "MCU") (pin "80") (pinfunction "PC12_80") (pintype "bidirectional"))
    )
    (net (code "145") (name "unconnected-(MCU-PC13-Pad7)") (class "Default")
      (node (ref "MCU") (pin "7") (pinfunction "PC13_7") (pintype "bidirectional"))
    )
    (net (code "146") (name "unconnected-(MCU-PC14-Pad8)") (class "Default")
      (node (ref "MCU") (pin "8") (pinfunction "PC14_8") (pintype "bidirectional"))
    )
    (net (code "147") (name "unconnected-(MCU-PC15-Pad9)") (class "Default")
      (node (ref "MCU") (pin "9") (pinfunction "PC15_9") (pintype "bidirectional"))
    )
    (net (code "148") (name "unconnected-(MCU-PD0-Pad81)") (class "Default")
      (node (ref "MCU") (pin "81") (pinfunction "PD0_81") (pintype "bidirectional"))
    )
    (net (code "149") (name "unconnected-(MCU-PD1-Pad82)") (class "Default")
      (node (ref "MCU") (pin "82") (pinfunction "PD1_82") (pintype "bidirectional"))
    )
    (net (code "150") (name "unconnected-(MCU-PD2-Pad83)") (class "Default")
      (node (ref "MCU") (pin "83") (pinfunction "PD2_83") (pintype "bidirectional"))
    )
    (net (code "151") (name "unconnected-(MCU-PD3-Pad84)") (class "Default")
      (node (ref "MCU") (pin "84") (pinfunction "PD3_84") (pintype "bidirectional"))
    )
    (net (code "152") (name "unconnected-(MCU-PD4-Pad85)") (class "Default")
      (node (ref "MCU") (pin "85") (pinfunction "PD4_85") (pintype "bidirectional"))
    )
    (net (code "153") (name "unconnected-(MCU-PD5-Pad86)") (class "Default")
      (node (ref "MCU") (pin "86") (pinfunction "PD5_86") (pintype "bidirectional"))
    )
    (net (code "154") (name "unconnected-(MCU-PD6-Pad87)") (class "Default")
      (node (ref "MCU") (pin "87") (pinfunction "PD6_87") (pintype "bidirectional"))
    )
    (net (code "155") (name "unconnected-(MCU-PD7-Pad88)") (class "Default")
      (node (ref "MCU") (pin "88") (pinfunction "PD7_88") (pintype "bidirectional"))
    )
    (net (code "156") (name "unconnected-(MCU-PD8-Pad55)") (class "Default")
      (node (ref "MCU") (pin "55") (pinfunction "PD8_55") (pintype "bidirectional"))
    )
    (net (code "157") (name "unconnected-(MCU-PD9-Pad56)") (class "Default")
      (node (ref "MCU") (pin "56") (pinfunction "PD9_56") (pintype "bidirectional"))
    )
    (net (code "158") (name "unconnected-(MCU-PD10-Pad57)") (class "Default")
      (node (ref "MCU") (pin "57") (pinfunction "PD10_57") (pintype "bidirectional"))
    )
    (net (code "159") (name "unconnected-(MCU-PD11-Pad58)") (class "Default")
      (node (ref "MCU") (pin "58") (pinfunction "PD11_58") (pintype "bidirectional"))
    )
    (net (code "160") (name "unconnected-(MCU-PD12-Pad59)") (class "Default")
      (node (ref "MCU") (pin "59") (pinfunction "PD12_59") (pintype "bidirectional"))
    )
    (net (code "161") (name "unconnected-(MCU-PD13-Pad60)") (class "Default")
      (node (ref "MCU") (pin "60") (pinfunction "PD13_60") (pintype "bidirectional"))
    )
    (net (code "162") (name "unconnected-(MCU-PD14-Pad61)") (class "Default")
      (node (ref "MCU") (pin "61") (pinfunction "PD14_61") (pintype "bidirectional"))
    )
    (net (code "163") (name "unconnected-(MCU-PD15-Pad62)") (class "Default")
      (node (ref "MCU") (pin "62") (pinfunction "PD15_62") (pintype "bidirectional"))
    )
    (net (code "164") (name "unconnected-(MCU-PE0-Pad97)") (class "Default")
      (node (ref "MCU") (pin "97") (pinfunction "PE0_97") (pintype "bidirectional"))
    )
    (net (code "165") (name "unconnected-(MCU-PE1-Pad98)") (class "Default")
      (node (ref "MCU") (pin "98") (pinfunction "PE1_98") (pintype "bidirectional"))
    )
    (net (code "166") (name "unconnected-(MCU-PE2-Pad1)") (class "Default")
      (node (ref "MCU") (pin "1") (pinfunction "PE2_1") (pintype "bidirectional"))
    )
    (net (code "167") (name "unconnected-(MCU-PE3-Pad2)") (class "Default")
      (node (ref "MCU") (pin "2") (pinfunction "PE3_2") (pintype "bidirectional"))
    )
    (net (code "168") (name "unconnected-(MCU-PE4-Pad3)") (class "Default")
      (node (ref "MCU") (pin "3") (pinfunction "PE4_3") (pintype "bidirectional"))
    )
    (net (code "169") (name "unconnected-(MCU-PE5-Pad4)") (class "Default")
      (node (ref "MCU") (pin "4") (pinfunction "PE5_4") (pintype "bidirectional"))
    )
    (net (code "170") (name "unconnected-(MCU-PE6-Pad5)") (class "Default")
      (node (ref "MCU") (pin "5") (pinfunction "PE6_5") (pintype "bidirectional"))
    )
    (net (code "171") (name "unconnected-(MCU-PE7-Pad37)") (class "Default")
      (node (ref "MCU") (pin "37") (pinfunction "PE7_37") (pintype "bidirectional"))
    )
    (net (code "172") (name "unconnected-(MCU-PE8-Pad38)") (class "Default")
      (node (ref "MCU") (pin "38") (pinfunction "PE8_38") (pintype "bidirectional"))
    )
    (net (code "173") (name "unconnected-(MCU-PE10-Pad40)") (class "Default")
      (node (ref "MCU") (pin "40") (pinfunction "PE10_40") (pintype "bidirectional"))
    )
    (net (code "174") (name "unconnected-(MCU-PE12-Pad42)") (class "Default")
      (node (ref "MCU") (pin "42") (pinfunction "PE12_42") (pintype "bidirectional"))
    )
    (net (code "175") (name "unconnected-(MCU-PE13-Pad43)") (class "Default")
      (node (ref "MCU") (pin "43") (pinfunction "PE13_43") (pintype "bidirectional"))
    )
    (net (code "176") (name "unconnected-(MCU-PE14-Pad44)") (class "Default")
      (node (ref "MCU") (pin "44") (pinfunction "PE14_44") (pintype "bidirectional"))
    )
    (net (code "177") (name "unconnected-(MCU-PE15-Pad45)") (class "Default")
      (node (ref "MCU") (pin "45") (pinfunction "PE15_45") (pintype "bidirectional"))
    )
    (net (code "178") (name "unconnected-(PUSHPULL-1A-Pad2)") (class "Default")
      (node (ref "PUSHPULL") (pin "2") (pinfunction "1A_2") (pintype "bidirectional"))
    )
    (net (code "179") (name "unconnected-(PUSHPULL-2A-Pad5)") (class "Default")
      (node (ref "PUSHPULL") (pin "5") (pinfunction "2A_5") (pintype "bidirectional"))
    )
  )
)
